# BatchC.net
KiCad netlist of a schematic drawn in EAGLE
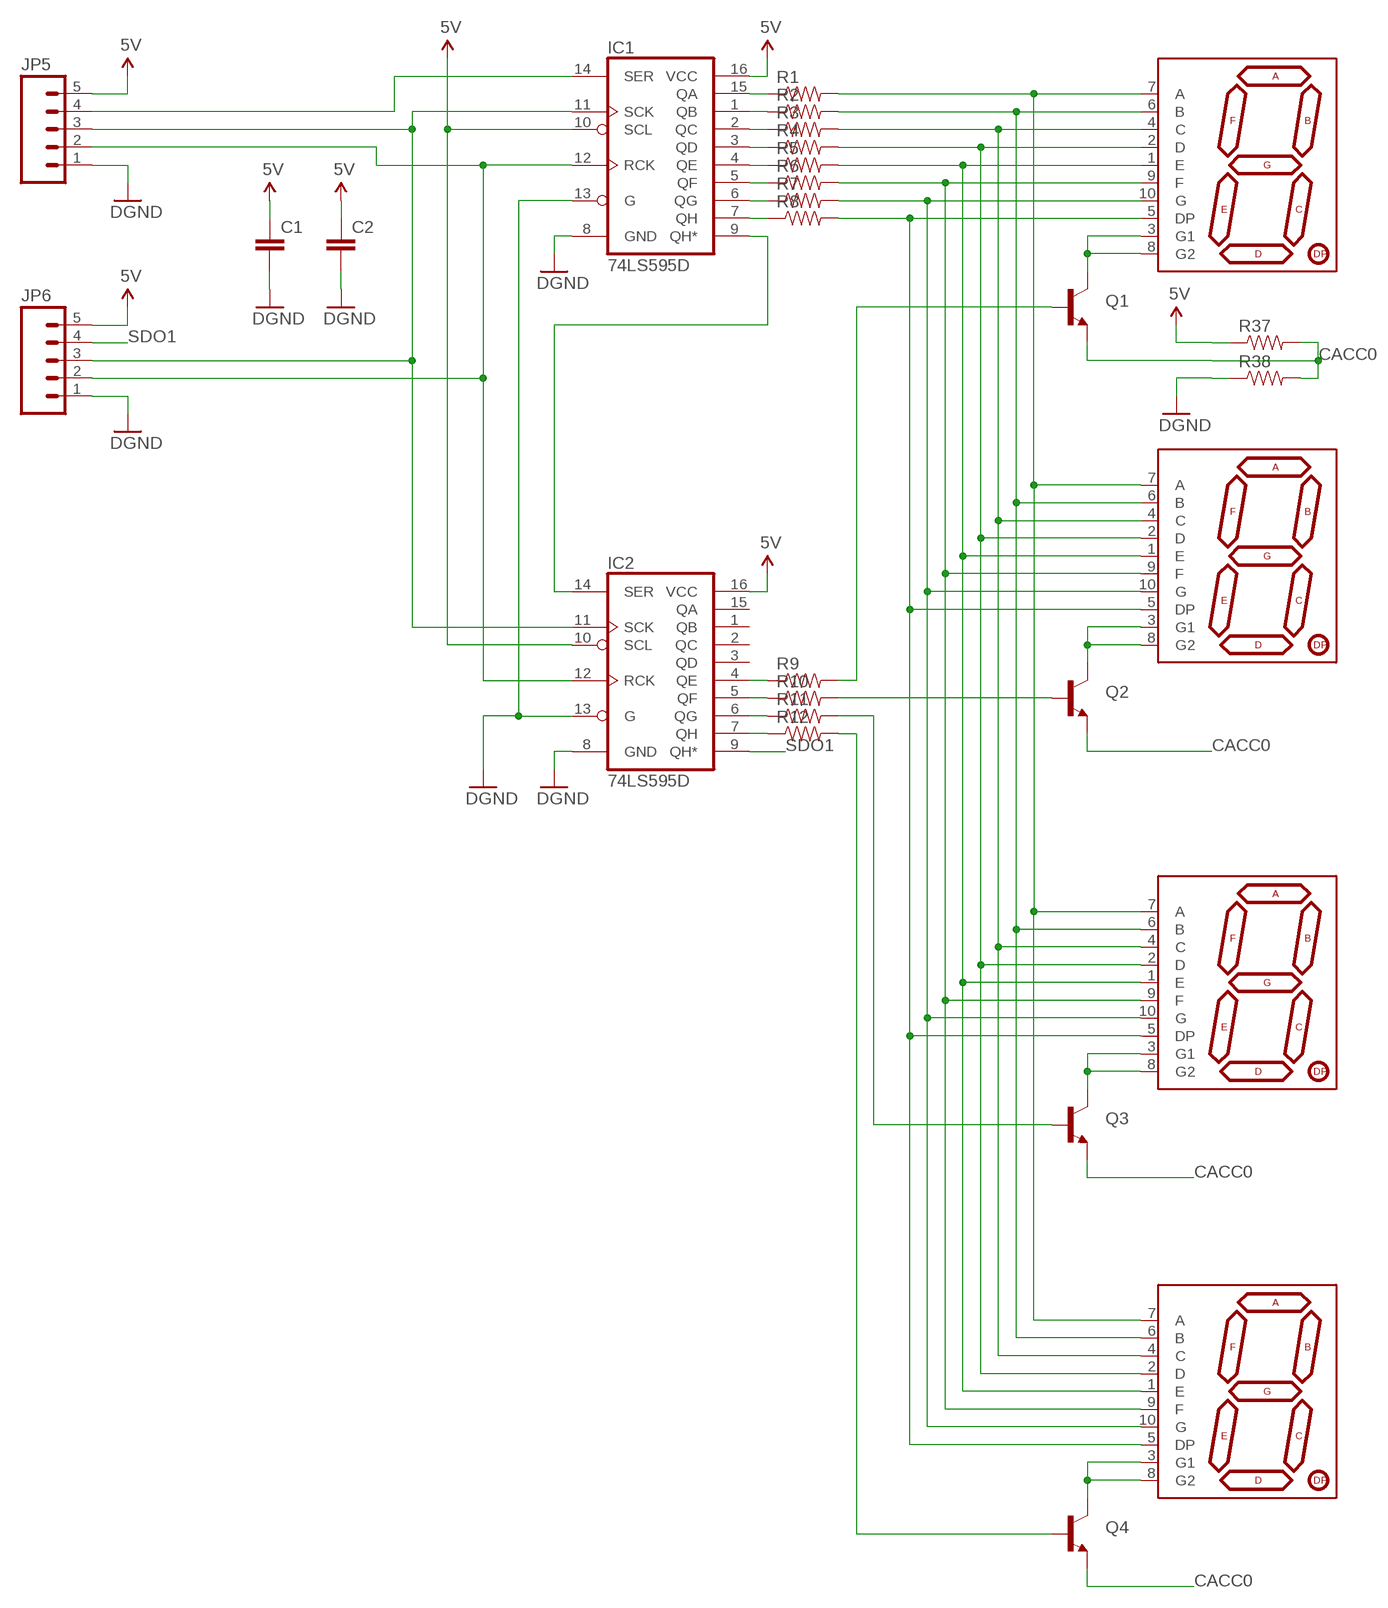
[diagram p0: schematic, sheet 1]
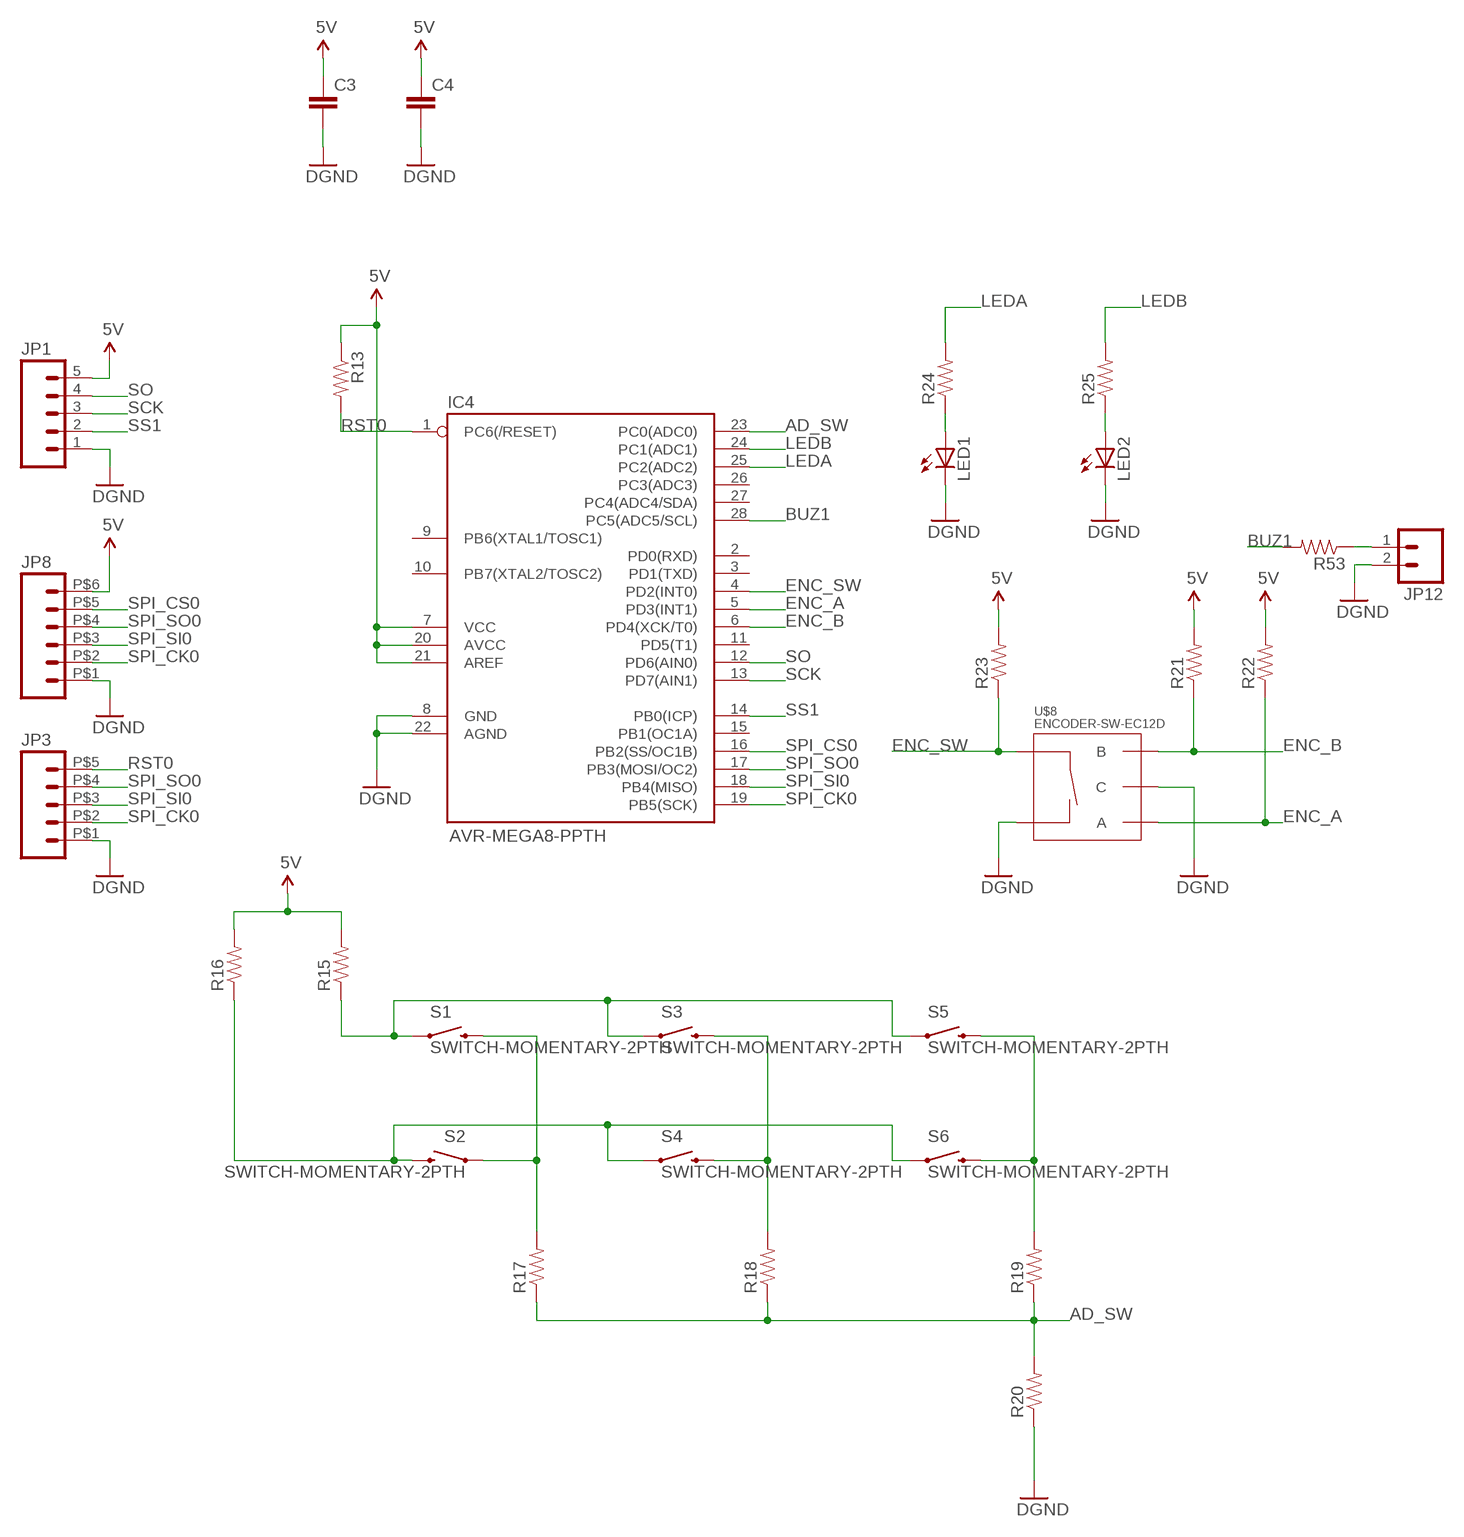
[diagram p1: schematic, sheet 2]
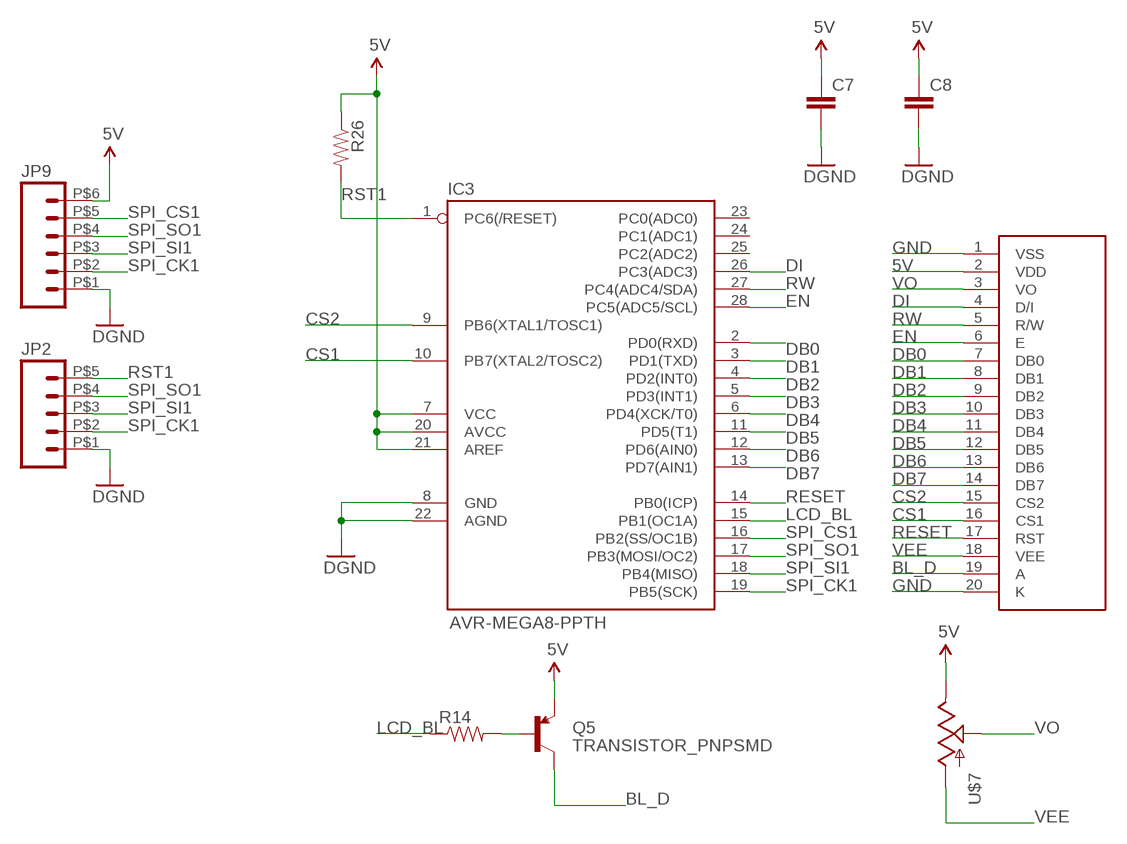
[diagram p2: schematic, sheet 3]
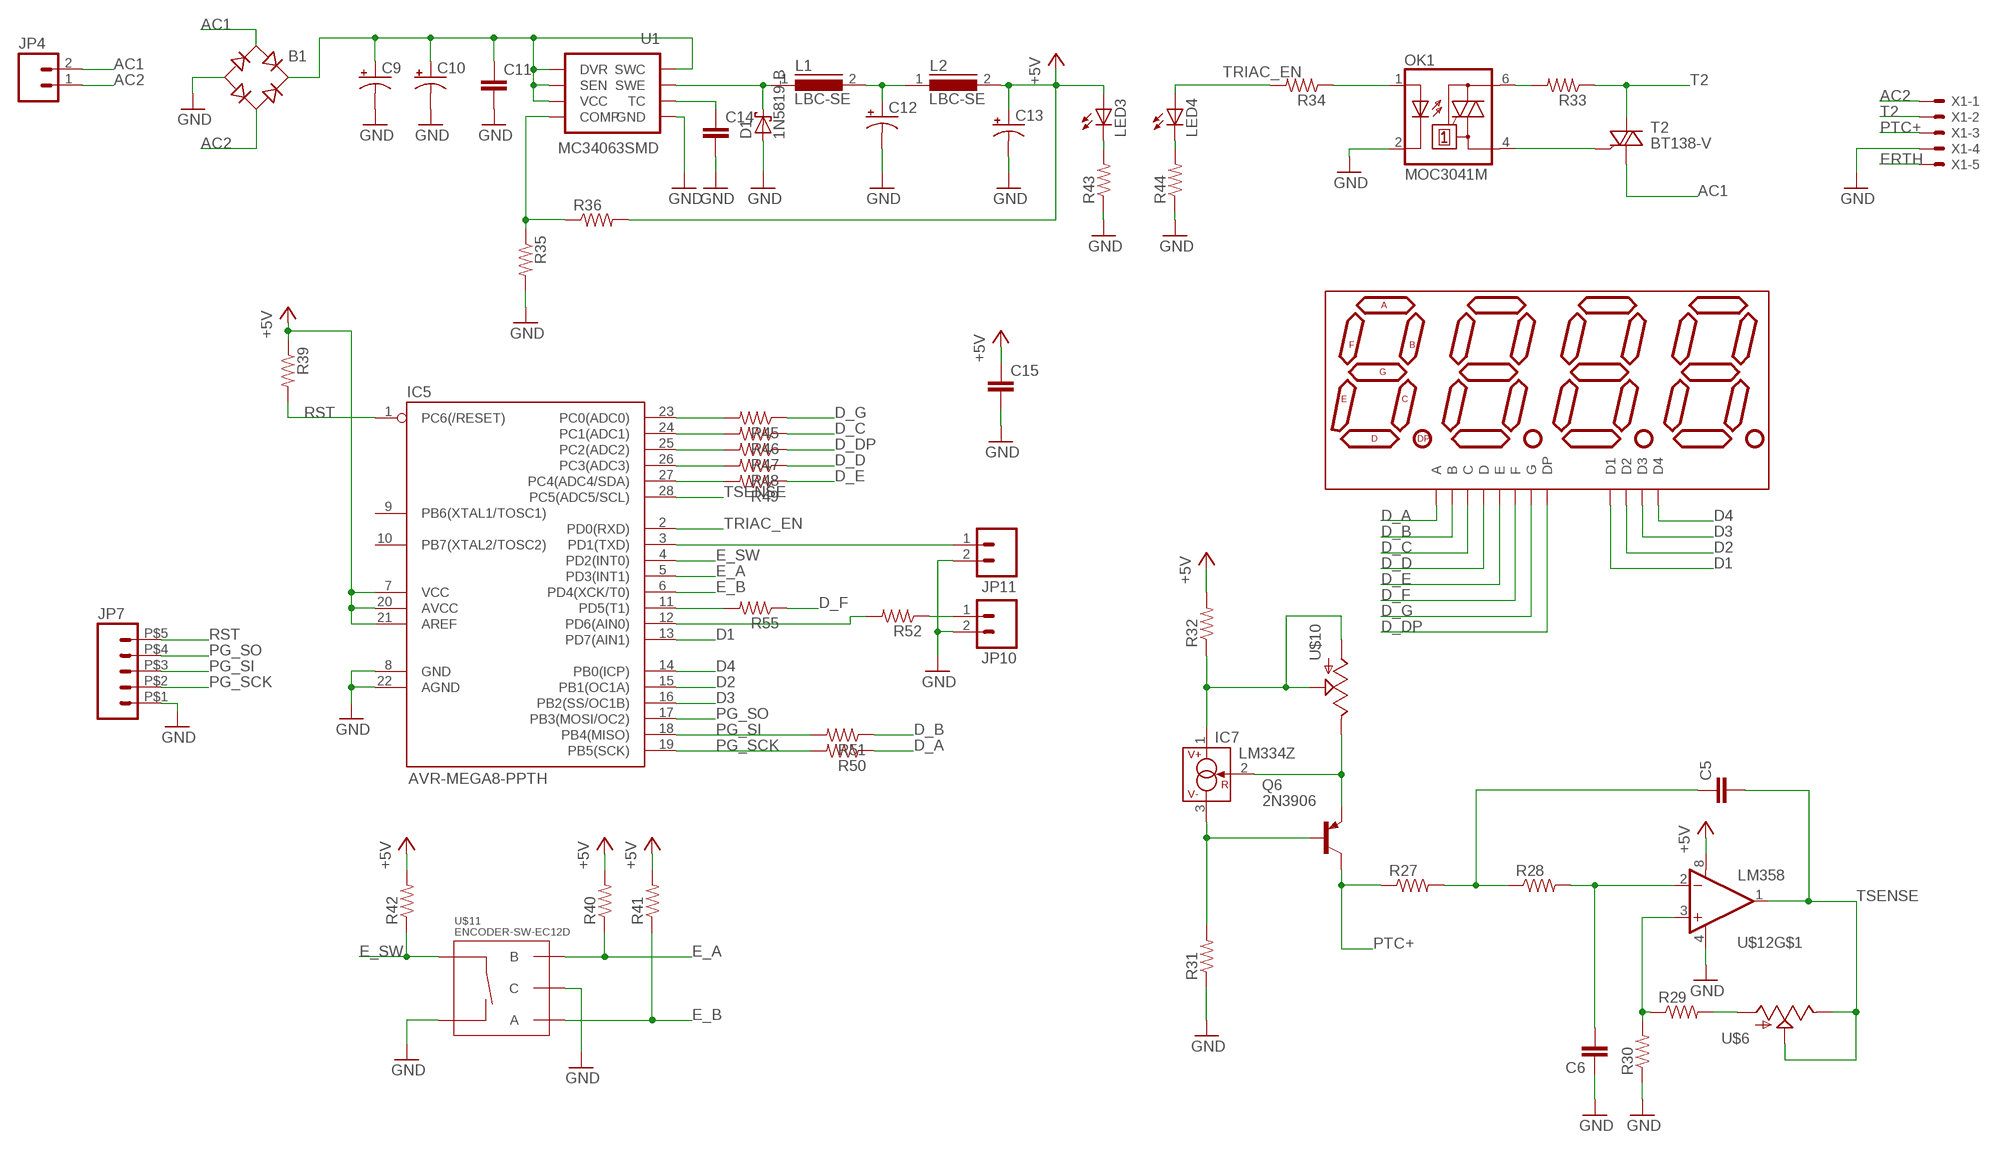
[diagram p3: schematic, sheet 4]
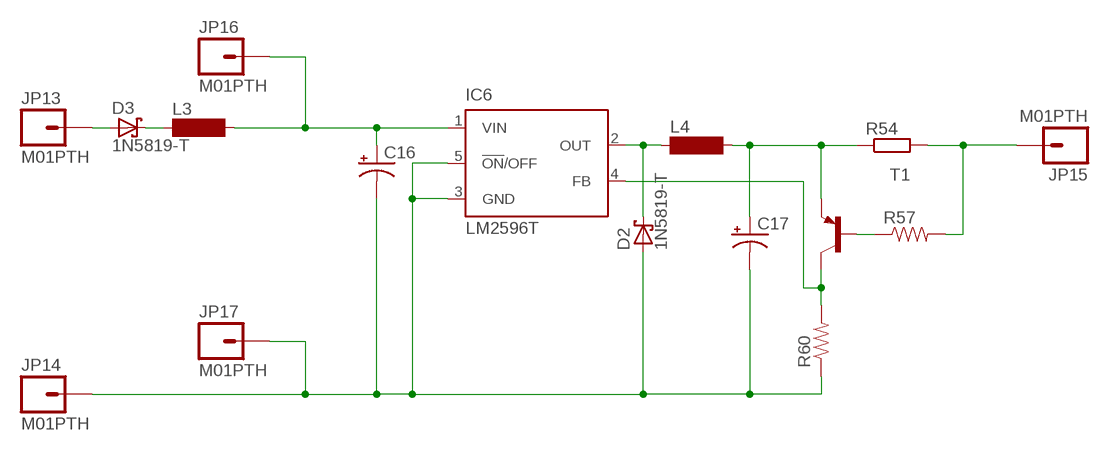
[diagram p4: schematic, sheet 5]

(export (version "E")
  (design (tool "Eeschema 10.0.6"))
  (components
    (comp (ref "C1")
      (value "CAP1206")
      (footprint "eagle-import:1206")
      (libsource (lib "eagle-import") (part "CAP1206"))
    )
    (comp (ref "C2")
      (value "CAP1206")
      (footprint "eagle-import:1206")
      (libsource (lib "eagle-import") (part "CAP1206"))
    )
    (comp (ref "IC1")
      (value "74LS595D")
      (footprint "eagle-import:SO16")
      (libsource (lib "eagle-import") (part "74595DLS"))
    )
    (comp (ref "IC2")
      (value "74LS595D")
      (footprint "eagle-import:SO16")
      (libsource (lib "eagle-import") (part "74595DLS"))
    )
    (comp (ref "JP5")
      (value "M05PTH")
      (footprint "eagle-import:1X05")
      (libsource (lib "eagle-import") (part "M05PTH"))
    )
    (comp (ref "JP6")
      (value "M05PTH")
      (footprint "eagle-import:1X05")
      (libsource (lib "eagle-import") (part "M05PTH"))
    )
    (comp (ref "Q1")
      (value "TRANSISTOR_NPNSOT23")
      (footprint "eagle-import:SOT23")
      (libsource (lib "eagle-import") (part "TRANSISTOR_NPNSOT23"))
    )
    (comp (ref "Q2")
      (value "TRANSISTOR_NPNSOT23")
      (footprint "eagle-import:SOT23")
      (libsource (lib "eagle-import") (part "TRANSISTOR_NPNSOT23"))
    )
    (comp (ref "Q3")
      (value "TRANSISTOR_NPNSOT23")
      (footprint "eagle-import:SOT23")
      (libsource (lib "eagle-import") (part "TRANSISTOR_NPNSOT23"))
    )
    (comp (ref "Q4")
      (value "TRANSISTOR_NPNSOT23")
      (footprint "eagle-import:SOT23")
      (libsource (lib "eagle-import") (part "TRANSISTOR_NPNSOT23"))
    )
    (comp (ref "R1")
      (value "RESISTOR0805-RES")
      (footprint "eagle-import:0805")
      (libsource (lib "eagle-import") (part "RESISTOR0805-RES"))
    )
    (comp (ref "R2")
      (value "RESISTOR0805-RES")
      (footprint "eagle-import:0805")
      (libsource (lib "eagle-import") (part "RESISTOR0805-RES"))
    )
    (comp (ref "R3")
      (value "RESISTOR0805-RES")
      (footprint "eagle-import:0805")
      (libsource (lib "eagle-import") (part "RESISTOR0805-RES"))
    )
    (comp (ref "R4")
      (value "RESISTOR0805-RES")
      (footprint "eagle-import:0805")
      (libsource (lib "eagle-import") (part "RESISTOR0805-RES"))
    )
    (comp (ref "R5")
      (value "RESISTOR0805-RES")
      (footprint "eagle-import:0805")
      (libsource (lib "eagle-import") (part "RESISTOR0805-RES"))
    )
    (comp (ref "R6")
      (value "RESISTOR0805-RES")
      (footprint "eagle-import:0805")
      (libsource (lib "eagle-import") (part "RESISTOR0805-RES"))
    )
    (comp (ref "R7")
      (value "RESISTOR0805-RES")
      (footprint "eagle-import:0805")
      (libsource (lib "eagle-import") (part "RESISTOR0805-RES"))
    )
    (comp (ref "R8")
      (value "RESISTOR0805-RES")
      (footprint "eagle-import:0805")
      (libsource (lib "eagle-import") (part "RESISTOR0805-RES"))
    )
    (comp (ref "R9")
      (value "RESISTOR0805-RES")
      (footprint "eagle-import:0805")
      (libsource (lib "eagle-import") (part "RESISTOR0805-RES"))
    )
    (comp (ref "R10")
      (value "RESISTOR0805-RES")
      (footprint "eagle-import:0805")
      (libsource (lib "eagle-import") (part "RESISTOR0805-RES"))
    )
    (comp (ref "R11")
      (value "RESISTOR0805-RES")
      (footprint "eagle-import:0805")
      (libsource (lib "eagle-import") (part "RESISTOR0805-RES"))
    )
    (comp (ref "R12")
      (value "RESISTOR0805-RES")
      (footprint "eagle-import:0805")
      (libsource (lib "eagle-import") (part "RESISTOR0805-RES"))
    )
    (comp (ref "R37")
      (value "RESISTOR0805-RES")
      (footprint "eagle-import:0805")
      (libsource (lib "eagle-import") (part "RESISTOR0805-RES"))
    )
    (comp (ref "R38")
      (value "RESISTOR0805-RES")
      (footprint "eagle-import:0805")
      (libsource (lib "eagle-import") (part "RESISTOR0805-RES"))
    )
    (comp (ref "U$1")
      (value "7-SEGMENT-DISPLAYPTH")
      (footprint "eagle-import:7-SEGMENT-DISPLAY")
      (libsource (lib "eagle-import") (part "7-SEGMENT-DISPLAYPTH"))
    )
    (comp (ref "U$2")
      (value "7-SEGMENT-DISPLAYPTH")
      (footprint "eagle-import:7-SEGMENT-DISPLAY")
      (libsource (lib "eagle-import") (part "7-SEGMENT-DISPLAYPTH"))
    )
    (comp (ref "U$3")
      (value "7-SEGMENT-DISPLAYPTH")
      (footprint "eagle-import:7-SEGMENT-DISPLAY")
      (libsource (lib "eagle-import") (part "7-SEGMENT-DISPLAYPTH"))
    )
    (comp (ref "U$4")
      (value "7-SEGMENT-DISPLAYPTH")
      (footprint "eagle-import:7-SEGMENT-DISPLAY")
      (libsource (lib "eagle-import") (part "7-SEGMENT-DISPLAYPTH"))
    )
    (comp (ref "B1")
      (value "RB1A")
      (footprint "eagle-import:RB1A")
      (libsource (lib "eagle-import") (part "RB1A"))
    )
    (comp (ref "C5")
      (value "CAPPTH")
      (footprint "eagle-import:CAP-PTH-SMALL")
      (libsource (lib "eagle-import") (part "CAPPTH"))
    )
    (comp (ref "C6")
      (value "CAPPTH")
      (footprint "eagle-import:CAP-PTH-SMALL")
      (libsource (lib "eagle-import") (part "CAPPTH"))
    )
    (comp (ref "C9")
      (value "CAP_POLPTH1")
      (footprint "eagle-import:CPOL-RADIAL-100UF-25V")
      (libsource (lib "eagle-import") (part "CAP_POLPTH1"))
    )
    (comp (ref "C10")
      (value "CAP_POLPTH1")
      (footprint "eagle-import:CPOL-RADIAL-100UF-25V")
      (libsource (lib "eagle-import") (part "CAP_POLPTH1"))
    )
    (comp (ref "C11")
      (value "CAP1206")
      (footprint "eagle-import:1206")
      (libsource (lib "eagle-import") (part "CAP1206"))
    )
    (comp (ref "C12")
      (value "CAP_POLPTH1")
      (footprint "eagle-import:CPOL-RADIAL-100UF-25V")
      (libsource (lib "eagle-import") (part "CAP_POLPTH1"))
    )
    (comp (ref "C13")
      (value "CAP_POLPTH1")
      (footprint "eagle-import:CPOL-RADIAL-100UF-25V")
      (libsource (lib "eagle-import") (part "CAP_POLPTH1"))
    )
    (comp (ref "C14")
      (value "CAP1206")
      (footprint "eagle-import:1206")
      (libsource (lib "eagle-import") (part "CAP1206"))
    )
    (comp (ref "C15")
      (value "CAP1206")
      (footprint "eagle-import:1206")
      (libsource (lib "eagle-import") (part "CAP1206"))
    )
    (comp (ref "D1")
      (value "1N5819-B")
      (footprint "eagle-import:DO41-7.6")
      (libsource (lib "eagle-import") (part "1N5819-B"))
    )
    (comp (ref "IC5")
      (value "AVR-MEGA8-PPTH")
      (footprint "eagle-import:DIL28-3")
      (libsource (lib "eagle-import") (part "AVR-MEGA8-PPTH"))
    )
    (comp (ref "IC7")
      (value "LM334Z")
      (footprint "eagle-import:TO92")
      (libsource (lib "eagle-import") (part "LM34Z3"))
    )
    (comp (ref "JP4")
      (value "M023.5MM")
      (footprint "eagle-import:SCREWTERMINAL-3.5MM-2")
      (libsource (lib "eagle-import") (part "M023.5MM"))
    )
    (comp (ref "JP7")
      (value "M05")
      (footprint "eagle-import:1X05_SMALLPADS")
      (libsource (lib "eagle-import") (part "M05"))
    )
    (comp (ref "JP10")
      (value "M02PTH")
      (footprint "eagle-import:1X02")
      (libsource (lib "eagle-import") (part "M02PTH"))
    )
    (comp (ref "JP11")
      (value "M02PTH")
      (footprint "eagle-import:1X02")
      (libsource (lib "eagle-import") (part "M02PTH"))
    )
    (comp (ref "L1")
      (value "LBC-SE")
      (footprint "eagle-import:LBC-SE")
      (libsource (lib "eagle-import") (part "LBC-SE"))
    )
    (comp (ref "L2")
      (value "LBC-SE")
      (footprint "eagle-import:LBC-SE")
      (libsource (lib "eagle-import") (part "LBC-SE"))
    )
    (comp (ref "LED3")
      (value "LED3MM")
      (footprint "eagle-import:LED3MM")
      (libsource (lib "eagle-import") (part "LED3MM"))
    )
    (comp (ref "LED4")
      (value "LED3MM")
      (footprint "eagle-import:LED3MM")
      (libsource (lib "eagle-import") (part "LED3MM"))
    )
    (comp (ref "OK1")
      (value "MOC3041M")
      (footprint "eagle-import:DIL06")
      (fields (field (name "MF") "FAIRCHILD SEMICONDUCTOR"))
      (libsource (lib "eagle-import") (part "MOC3041M"))
    )
    (comp (ref "Q6")
      (value "2N3906")
      (footprint "eagle-import:TO92")
      (libsource (lib "eagle-import") (part "2N3906"))
    )
    (comp (ref "R27")
      (value "RESISTOR0603-RES")
      (footprint "eagle-import:0603-RES")
      (libsource (lib "eagle-import") (part "SparkFun-Resistors_RESISTOR0603-RES"))
    )
    (comp (ref "R28")
      (value "RESISTOR0603-RES")
      (footprint "eagle-import:0603-RES")
      (libsource (lib "eagle-import") (part "SparkFun-Resistors_RESISTOR0603-RES"))
    )
    (comp (ref "R29")
      (value "RESISTOR0603-RES")
      (footprint "eagle-import:0603-RES")
      (libsource (lib "eagle-import") (part "SparkFun-Resistors_RESISTOR0603-RES"))
    )
    (comp (ref "R30")
      (value "RESISTOR0603-RES")
      (footprint "eagle-import:0603-RES")
      (libsource (lib "eagle-import") (part "SparkFun-Resistors_RESISTOR0603-RES"))
    )
    (comp (ref "R31")
      (value "RESISTOR0603-RES")
      (footprint "eagle-import:0603-RES")
      (libsource (lib "eagle-import") (part "SparkFun-Resistors_RESISTOR0603-RES"))
    )
    (comp (ref "R32")
      (value "RESISTOR0603-RES")
      (footprint "eagle-import:0603-RES")
      (libsource (lib "eagle-import") (part "SparkFun-Resistors_RESISTOR0603-RES"))
    )
    (comp (ref "R33")
      (value "RESISTOR0603-RES")
      (footprint "eagle-import:0603-RES")
      (libsource (lib "eagle-import") (part "SparkFun-Resistors_RESISTOR0603-RES"))
    )
    (comp (ref "R34")
      (value "RESISTOR0603-RES")
      (footprint "eagle-import:0603-RES")
      (libsource (lib "eagle-import") (part "SparkFun-Resistors_RESISTOR0603-RES"))
    )
    (comp (ref "R35")
      (value "RESISTOR0603-RES")
      (footprint "eagle-import:0603-RES")
      (libsource (lib "eagle-import") (part "SparkFun-Resistors_RESISTOR0603-RES"))
    )
    (comp (ref "R36")
      (value "RESISTOR0603-RES")
      (footprint "eagle-import:0603-RES")
      (libsource (lib "eagle-import") (part "SparkFun-Resistors_RESISTOR0603-RES"))
    )
    (comp (ref "R39")
      (value "RESISTOR0603-RES")
      (footprint "eagle-import:0603-RES")
      (libsource (lib "eagle-import") (part "SparkFun-Resistors_RESISTOR0603-RES"))
    )
    (comp (ref "R40")
      (value "RESISTOR0603-RES")
      (footprint "eagle-import:0603-RES")
      (libsource (lib "eagle-import") (part "SparkFun-Resistors_RESISTOR0603-RES"))
    )
    (comp (ref "R41")
      (value "RESISTOR0603-RES")
      (footprint "eagle-import:0603-RES")
      (libsource (lib "eagle-import") (part "SparkFun-Resistors_RESISTOR0603-RES"))
    )
    (comp (ref "R42")
      (value "RESISTOR0603-RES")
      (footprint "eagle-import:0603-RES")
      (libsource (lib "eagle-import") (part "SparkFun-Resistors_RESISTOR0603-RES"))
    )
    (comp (ref "R43")
      (value "RESISTOR0603-RES")
      (footprint "eagle-import:0603-RES")
      (libsource (lib "eagle-import") (part "SparkFun-Resistors_RESISTOR0603-RES"))
    )
    (comp (ref "R44")
      (value "RESISTOR0603-RES")
      (footprint "eagle-import:0603-RES")
      (libsource (lib "eagle-import") (part "SparkFun-Resistors_RESISTOR0603-RES"))
    )
    (comp (ref "R45")
      (value "RESISTOR0603-RES")
      (footprint "eagle-import:0603-RES")
      (libsource (lib "eagle-import") (part "SparkFun-Resistors_RESISTOR0603-RES"))
    )
    (comp (ref "R46")
      (value "RESISTOR0603-RES")
      (footprint "eagle-import:0603-RES")
      (libsource (lib "eagle-import") (part "SparkFun-Resistors_RESISTOR0603-RES"))
    )
    (comp (ref "R47")
      (value "RESISTOR0603-RES")
      (footprint "eagle-import:0603-RES")
      (libsource (lib "eagle-import") (part "SparkFun-Resistors_RESISTOR0603-RES"))
    )
    (comp (ref "R48")
      (value "RESISTOR0603-RES")
      (footprint "eagle-import:0603-RES")
      (libsource (lib "eagle-import") (part "SparkFun-Resistors_RESISTOR0603-RES"))
    )
    (comp (ref "R49")
      (value "RESISTOR0603-RES")
      (footprint "eagle-import:0603-RES")
      (libsource (lib "eagle-import") (part "SparkFun-Resistors_RESISTOR0603-RES"))
    )
    (comp (ref "R50")
      (value "RESISTOR0603-RES")
      (footprint "eagle-import:0603-RES")
      (libsource (lib "eagle-import") (part "SparkFun-Resistors_RESISTOR0603-RES"))
    )
    (comp (ref "R51")
      (value "RESISTOR0603-RES")
      (footprint "eagle-import:0603-RES")
      (libsource (lib "eagle-import") (part "SparkFun-Resistors_RESISTOR0603-RES"))
    )
    (comp (ref "R52")
      (value "RESISTOR0603-RES")
      (footprint "eagle-import:0603-RES")
      (libsource (lib "eagle-import") (part "SparkFun-Resistors_RESISTOR0603-RES"))
    )
    (comp (ref "R55")
      (value "RESISTOR0603-RES")
      (footprint "eagle-import:0603-RES")
      (libsource (lib "eagle-import") (part "SparkFun-Resistors_RESISTOR0603-RES"))
    )
    (comp (ref "T2")
      (value "BT138-V")
      (footprint "eagle-import:TO220BV")
      (libsource (lib "eagle-import") (part "BT138-V"))
    )
    (comp (ref "U$5")
      (value "7-SEGMENT-4DIGIT-COUNTER")
      (footprint "eagle-import:7-SEGMENT-4DIGIT-TPS")
      (libsource (lib "eagle-import") (part "7-SEGMENT-4DIGIT-COUNTER"))
    )
    (comp (ref "U$6")
      (value "POTTRIM")
      (footprint "eagle-import:TRIM_POT")
      (libsource (lib "eagle-import") (part "POTTRIM"))
    )
    (comp (ref "U$10")
      (value "POTTRIM")
      (footprint "eagle-import:TRIM_POT")
      (libsource (lib "eagle-import") (part "POTTRIM"))
    )
    (comp (ref "U$11")
      (value "ENCODER-SW-EC12D")
      (footprint "eagle-import:ENCODER-SW-EC12D")
      (libsource (lib "eagle-import") (part "ENCODER-SW-EC12D"))
    )
    (comp (ref "U$12")
      (value "LM358")
      (footprint "eagle-import:DIP08")
      (libsource (lib "eagle-import") (part "LM358"))
    )
    (comp (ref "U1")
      (value "MC34063SMD")
      (footprint "eagle-import:SO08")
      (libsource (lib "eagle-import") (part "MC34063SMD"))
    )
    (comp (ref "X1")
      (value "KK-156-5")
      (footprint "eagle-import:KK-156-5")
      (libsource (lib "eagle-import") (part "KK-156-5"))
    )
    (comp (ref "C3")
      (value "CAP1206")
      (footprint "eagle-import:1206")
      (libsource (lib "eagle-import") (part "CAP1206"))
    )
    (comp (ref "C4")
      (value "CAP1206")
      (footprint "eagle-import:1206")
      (libsource (lib "eagle-import") (part "CAP1206"))
    )
    (comp (ref "IC4")
      (value "AVR-MEGA8-PPTH")
      (footprint "eagle-import:DIL28-3")
      (libsource (lib "eagle-import") (part "AVR-MEGA8-PPTH"))
    )
    (comp (ref "JP1")
      (value "M05PTH")
      (footprint "eagle-import:1X05")
      (libsource (lib "eagle-import") (part "M05PTH"))
    )
    (comp (ref "JP3")
      (value "M05")
      (footprint "eagle-import:1X05_SMALLPADS")
      (libsource (lib "eagle-import") (part "M05"))
    )
    (comp (ref "JP8")
      (value "M06")
      (footprint "eagle-import:1X06_SMALLPADS")
      (libsource (lib "eagle-import") (part "M06"))
    )
    (comp (ref "JP12")
      (value "M02PTH")
      (footprint "eagle-import:1X02")
      (libsource (lib "eagle-import") (part "M02PTH"))
    )
    (comp (ref "LED1")
      (value "LED3MM")
      (footprint "eagle-import:LED3MM")
      (libsource (lib "eagle-import") (part "LED3MM"))
    )
    (comp (ref "LED2")
      (value "LED3MM")
      (footprint "eagle-import:LED3MM")
      (libsource (lib "eagle-import") (part "LED3MM"))
    )
    (comp (ref "R13")
      (value "RESISTOR0805-RES")
      (footprint "eagle-import:0805")
      (libsource (lib "eagle-import") (part "RESISTOR0805-RES"))
    )
    (comp (ref "R15")
      (value "RESISTOR0805-RES")
      (footprint "eagle-import:0805")
      (libsource (lib "eagle-import") (part "RESISTOR0805-RES"))
    )
    (comp (ref "R16")
      (value "RESISTOR0805-RES")
      (footprint "eagle-import:0805")
      (libsource (lib "eagle-import") (part "RESISTOR0805-RES"))
    )
    (comp (ref "R17")
      (value "RESISTOR0805-RES")
      (footprint "eagle-import:0805")
      (libsource (lib "eagle-import") (part "RESISTOR0805-RES"))
    )
    (comp (ref "R18")
      (value "RESISTOR0805-RES")
      (footprint "eagle-import:0805")
      (libsource (lib "eagle-import") (part "RESISTOR0805-RES"))
    )
    (comp (ref "R19")
      (value "RESISTOR0805-RES")
      (footprint "eagle-import:0805")
      (libsource (lib "eagle-import") (part "RESISTOR0805-RES"))
    )
    (comp (ref "R20")
      (value "RESISTOR0805-RES")
      (footprint "eagle-import:0805")
      (libsource (lib "eagle-import") (part "RESISTOR0805-RES"))
    )
    (comp (ref "R21")
      (value "RESISTOR0805-RES")
      (footprint "eagle-import:0805")
      (libsource (lib "eagle-import") (part "RESISTOR0805-RES"))
    )
    (comp (ref "R22")
      (value "RESISTOR0805-RES")
      (footprint "eagle-import:0805")
      (libsource (lib "eagle-import") (part "RESISTOR0805-RES"))
    )
    (comp (ref "R23")
      (value "RESISTOR0805-RES")
      (footprint "eagle-import:0805")
      (libsource (lib "eagle-import") (part "RESISTOR0805-RES"))
    )
    (comp (ref "R24")
      (value "RESISTOR0805-RES")
      (footprint "eagle-import:0805")
      (libsource (lib "eagle-import") (part "RESISTOR0805-RES"))
    )
    (comp (ref "R25")
      (value "RESISTOR0805-RES")
      (footprint "eagle-import:0805")
      (libsource (lib "eagle-import") (part "RESISTOR0805-RES"))
    )
    (comp (ref "R53")
      (value "RESISTOR0805-RES")
      (footprint "eagle-import:0805")
      (libsource (lib "eagle-import") (part "RESISTOR0805-RES"))
    )
    (comp (ref "S1")
      (value "SWITCH-MOMENTARY-2PTH")
      (footprint "eagle-import:TACTILE-PTH")
      (libsource (lib "eagle-import") (part "SWITCH-MOMENTARY-2PTH"))
    )
    (comp (ref "S2")
      (value "SWITCH-MOMENTARY-2PTH")
      (footprint "eagle-import:TACTILE-PTH")
      (libsource (lib "eagle-import") (part "SWITCH-MOMENTARY-2PTH"))
    )
    (comp (ref "S3")
      (value "SWITCH-MOMENTARY-2PTH")
      (footprint "eagle-import:TACTILE-PTH")
      (libsource (lib "eagle-import") (part "SWITCH-MOMENTARY-2PTH"))
    )
    (comp (ref "S4")
      (value "SWITCH-MOMENTARY-2PTH")
      (footprint "eagle-import:TACTILE-PTH")
      (libsource (lib "eagle-import") (part "SWITCH-MOMENTARY-2PTH"))
    )
    (comp (ref "S5")
      (value "SWITCH-MOMENTARY-2PTH")
      (footprint "eagle-import:TACTILE-PTH")
      (libsource (lib "eagle-import") (part "SWITCH-MOMENTARY-2PTH"))
    )
    (comp (ref "S6")
      (value "SWITCH-MOMENTARY-2PTH")
      (footprint "eagle-import:TACTILE-PTH")
      (libsource (lib "eagle-import") (part "SWITCH-MOMENTARY-2PTH"))
    )
    (comp (ref "U$8")
      (value "ENCODER-SW-EC12D")
      (footprint "eagle-import:ENCODER-SW-EC12D")
      (libsource (lib "eagle-import") (part "ENCODER-SW-EC12D"))
    )
    (comp (ref "C7")
      (value "CAP1206")
      (footprint "eagle-import:1206")
      (libsource (lib "eagle-import") (part "CAP1206"))
    )
    (comp (ref "C8")
      (value "CAP1206")
      (footprint "eagle-import:1206")
      (libsource (lib "eagle-import") (part "CAP1206"))
    )
    (comp (ref "IC3")
      (value "AVR-MEGA8-PPTH")
      (footprint "eagle-import:DIL28-3")
      (libsource (lib "eagle-import") (part "AVR-MEGA8-PPTH"))
    )
    (comp (ref "JP2")
      (value "M05")
      (footprint "eagle-import:1X05_SMALLPADS")
      (libsource (lib "eagle-import") (part "M05"))
    )
    (comp (ref "JP9")
      (value "M06")
      (footprint "eagle-import:1X06_SMALLPADS")
      (libsource (lib "eagle-import") (part "M06"))
    )
    (comp (ref "Q5")
      (value "TRANSISTOR_PNPSMD")
      (footprint "eagle-import:SOT23-3")
      (libsource (lib "eagle-import") (part "TRANSISTOR_PNPSMD"))
    )
    (comp (ref "R14")
      (value "RESISTOR0805-RES")
      (footprint "eagle-import:0805")
      (libsource (lib "eagle-import") (part "RESISTOR0805-RES"))
    )
    (comp (ref "R26")
      (value "RESISTOR0805-RES")
      (footprint "eagle-import:0805")
      (libsource (lib "eagle-import") (part "RESISTOR0805-RES"))
    )
    (comp (ref "U$7")
      (value "POTTRIM")
      (footprint "eagle-import:TRIM_POT")
      (libsource (lib "eagle-import") (part "POTTRIM"))
    )
    (comp (ref "U$9")
      (value "LCD-G12864BARE")
      (footprint "eagle-import:1X20")
      (libsource (lib "eagle-import") (part "LCD-G12864BARE"))
    )
    (comp (ref "C16")
      (value "CAP_POLPTH1")
      (footprint "eagle-import:CPOL-RADIAL-100UF-25V")
      (libsource (lib "eagle-import") (part "SparkFun-Passives_CAP_POLPTH1"))
    )
    (comp (ref "C17")
      (value "CAP_POLPTH1")
      (footprint "eagle-import:CPOL-RADIAL-100UF-25V")
      (libsource (lib "eagle-import") (part "SparkFun-Passives_CAP_POLPTH1"))
    )
    (comp (ref "D2")
      (value "1N5819-T")
      (footprint "eagle-import:DO41-7.6")
      (libsource (lib "eagle-import") (part "1N5819-T"))
    )
    (comp (ref "D3")
      (value "1N5819-T")
      (footprint "eagle-import:DO41-7.6")
      (libsource (lib "eagle-import") (part "1N5819-T"))
    )
    (comp (ref "IC6")
      (value "LM2596T")
      (footprint "eagle-import:T05D")
      (fields (field (name "MPN") "LM2596T-ADJ/LF02"))
      (libsource (lib "eagle-import") (part "LM2596T"))
    )
    (comp (ref "JP13")
      (value "M01PTH")
      (footprint "eagle-import:1X01")
      (libsource (lib "eagle-import") (part "M01PTH"))
    )
    (comp (ref "JP14")
      (value "M01PTH")
      (footprint "eagle-import:1X01")
      (libsource (lib "eagle-import") (part "M01PTH"))
    )
    (comp (ref "JP15")
      (value "M01PTH")
      (footprint "eagle-import:1X01")
      (libsource (lib "eagle-import") (part "M01PTH"))
    )
    (comp (ref "JP16")
      (value "M01PTH")
      (footprint "eagle-import:1X01")
      (libsource (lib "eagle-import") (part "M01PTH"))
    )
    (comp (ref "JP17")
      (value "M01PTH")
      (footprint "eagle-import:1X01")
      (libsource (lib "eagle-import") (part "M01PTH"))
    )
    (comp (ref "L3")
      (value "BS11")
      (footprint "eagle-import:BS11")
      (libsource (lib "eagle-import") (part "BS11"))
    )
    (comp (ref "L4")
      (value "BS11")
      (footprint "eagle-import:BS11")
      (libsource (lib "eagle-import") (part "BS11"))
    )
    (comp (ref "R54")
      (value "R-EU_0204/2V")
      (footprint "eagle-import:0204V")
      (libsource (lib "eagle-import") (part "R-EU_0204/2V"))
    )
    (comp (ref "R57")
      (value "RESISTOR1206")
      (footprint "eagle-import:1206")
      (libsource (lib "eagle-import") (part "SparkFun-Resistors_RESISTOR1206"))
    )
    (comp (ref "R60")
      (value "RESISTOR1206")
      (footprint "eagle-import:1206")
      (libsource (lib "eagle-import") (part "SparkFun-Resistors_RESISTOR1206"))
    )
    (comp (ref "T1")
      (value "BC857C-PNP-SOT23-BEC")
      (footprint "eagle-import:SOT23-BEC")
      (libsource (lib "eagle-import") (part "-PNP-SOT23-BECBC857C"))
    )
  )
  (nets
    (net (code "1") (name "+5V") (class "Default")
      (node (ref "C13") (pin "1") (pinfunction "+_1") (pintype "passive"))
      (node (ref "C15") (pin "1") (pinfunction "1_1") (pintype "passive"))
      (node (ref "IC5") (pin "20") (pinfunction "AVCC_20") (pintype "bidirectional"))
      (node (ref "IC5") (pin "21") (pinfunction "AREF_21") (pintype "bidirectional"))
      (node (ref "IC5") (pin "7") (pinfunction "VCC_7") (pintype "bidirectional"))
      (node (ref "L2") (pin "2") (pinfunction "2_2") (pintype "passive"))
      (node (ref "LED3") (pin "A") (pinfunction "A_A") (pintype "passive"))
      (node (ref "R32") (pin "2") (pinfunction "2_2") (pintype "passive"))
      (node (ref "R36") (pin "2") (pinfunction "2_2") (pintype "passive"))
      (node (ref "R39") (pin "1") (pinfunction "1_1") (pintype "passive"))
      (node (ref "R40") (pin "2") (pinfunction "2_2") (pintype "passive"))
      (node (ref "R41") (pin "2") (pinfunction "2_2") (pintype "passive"))
      (node (ref "R42") (pin "2") (pinfunction "2_2") (pintype "passive"))
      (node (ref "U$12") (pin "8") (pinfunction "V+_8") (pintype "power_in"))
    )
    (net (code "2") (name "5V") (class "Default")
      (node (ref "C1") (pin "1") (pinfunction "1_1") (pintype "passive"))
      (node (ref "C2") (pin "1") (pinfunction "1_1") (pintype "passive"))
      (node (ref "C3") (pin "1") (pinfunction "1_1") (pintype "passive"))
      (node (ref "C4") (pin "1") (pinfunction "1_1") (pintype "passive"))
      (node (ref "C7") (pin "1") (pinfunction "1_1") (pintype "passive"))
      (node (ref "C8") (pin "1") (pinfunction "1_1") (pintype "passive"))
      (node (ref "IC1") (pin "10") (pinfunction "SCL_10") (pintype "input"))
      (node (ref "IC1") (pin "16") (pinfunction "VCC_16") (pintype "power_in"))
      (node (ref "IC2") (pin "10") (pinfunction "SCL_10") (pintype "input"))
      (node (ref "IC2") (pin "16") (pinfunction "VCC_16") (pintype "power_in"))
      (node (ref "IC3") (pin "20") (pinfunction "AVCC_20") (pintype "bidirectional"))
      (node (ref "IC3") (pin "21") (pinfunction "AREF_21") (pintype "bidirectional"))
      (node (ref "IC3") (pin "7") (pinfunction "VCC_7") (pintype "bidirectional"))
      (node (ref "IC4") (pin "20") (pinfunction "AVCC_20") (pintype "bidirectional"))
      (node (ref "IC4") (pin "21") (pinfunction "AREF_21") (pintype "bidirectional"))
      (node (ref "IC4") (pin "7") (pinfunction "VCC_7") (pintype "bidirectional"))
      (node (ref "JP1") (pin "5") (pinfunction "5_5") (pintype "passive"))
      (node (ref "JP5") (pin "5") (pinfunction "5_5") (pintype "passive"))
      (node (ref "JP6") (pin "5") (pinfunction "5_5") (pintype "passive"))
      (node (ref "JP8") (pin "P$6") (pinfunction "6_P$6") (pintype "passive"))
      (node (ref "JP9") (pin "P$6") (pinfunction "6_P$6") (pintype "passive"))
      (node (ref "Q5") (pin "2") (pinfunction "E_2") (pintype "passive"))
      (node (ref "R13") (pin "1") (pinfunction "1_1") (pintype "passive"))
      (node (ref "R15") (pin "2") (pinfunction "2_2") (pintype "passive"))
      (node (ref "R16") (pin "2") (pinfunction "2_2") (pintype "passive"))
      (node (ref "R21") (pin "2") (pinfunction "2_2") (pintype "passive"))
      (node (ref "R22") (pin "2") (pinfunction "2_2") (pintype "passive"))
      (node (ref "R23") (pin "2") (pinfunction "2_2") (pintype "passive"))
      (node (ref "R26") (pin "1") (pinfunction "1_1") (pintype "passive"))
      (node (ref "R37") (pin "1") (pinfunction "1_1") (pintype "passive"))
      (node (ref "U$7") (pin "2") (pinfunction "E_2") (pintype "passive"))
      (node (ref "U$9") (pin "2") (pinfunction "VDD_2") (pintype "power_in"))
    )
    (net (code "3") (name "AC1") (class "Default")
      (node (ref "B1") (pin "AC1") (pinfunction "AC1_AC1") (pintype "passive"))
      (node (ref "JP4") (pin "2") (pinfunction "2_2") (pintype "passive"))
      (node (ref "T2") (pin "T1") (pinfunction "A1_T1") (pintype "passive"))
    )
    (net (code "4") (name "AC2") (class "Default")
      (node (ref "B1") (pin "AC2") (pinfunction "AC2_AC2") (pintype "passive"))
      (node (ref "JP4") (pin "1") (pinfunction "1_1") (pintype "passive"))
      (node (ref "X1") (pin "1") (pinfunction "S_1") (pintype "passive"))
    )
    (net (code "5") (name "AD_SW") (class "Default")
      (node (ref "IC4") (pin "23") (pinfunction "PC0(ADC0)_23") (pintype "bidirectional"))
      (node (ref "R17") (pin "1") (pinfunction "1_1") (pintype "passive"))
      (node (ref "R18") (pin "1") (pinfunction "1_1") (pintype "passive"))
      (node (ref "R19") (pin "1") (pinfunction "1_1") (pintype "passive"))
      (node (ref "R20") (pin "2") (pinfunction "2_2") (pintype "passive"))
    )
    (net (code "6") (name "BL_D") (class "Default")
      (node (ref "Q5") (pin "3") (pinfunction "C_3") (pintype "passive"))
      (node (ref "U$9") (pin "19") (pinfunction "A_19") (pintype "power_in"))
    )
    (net (code "7") (name "BUZ1") (class "Default")
      (node (ref "IC4") (pin "28") (pinfunction "PC5(ADC5/SCL)_28") (pintype "bidirectional"))
      (node (ref "R53") (pin "2") (pinfunction "2_2") (pintype "passive"))
    )
    (net (code "8") (name "CACC0") (class "Default")
      (node (ref "Q1") (pin "2") (pinfunction "E_2") (pintype "passive"))
      (node (ref "Q2") (pin "2") (pinfunction "E_2") (pintype "passive"))
      (node (ref "Q3") (pin "2") (pinfunction "E_2") (pintype "passive"))
      (node (ref "Q4") (pin "2") (pinfunction "E_2") (pintype "passive"))
      (node (ref "R37") (pin "2") (pinfunction "2_2") (pintype "passive"))
      (node (ref "R38") (pin "2") (pinfunction "2_2") (pintype "passive"))
    )
    (net (code "9") (name "CS1") (class "Default")
      (node (ref "IC3") (pin "10") (pinfunction "PB7(XTAL2/TOSC2)_10") (pintype "bidirectional"))
      (node (ref "U$9") (pin "16") (pinfunction "CS1_16") (pintype "input"))
    )
    (net (code "10") (name "CS2") (class "Default")
      (node (ref "IC3") (pin "9") (pinfunction "PB6(XTAL1/TOSC1)_9") (pintype "bidirectional"))
      (node (ref "U$9") (pin "15") (pinfunction "CS2_15") (pintype "input"))
    )
    (net (code "11") (name "D1") (class "Default")
      (node (ref "IC5") (pin "13") (pinfunction "PD7(AIN1)_13") (pintype "bidirectional"))
      (node (ref "U$5") (pin "P$12") (pinfunction "D1_P$12") (pintype "bidirectional"))
    )
    (net (code "12") (name "D2") (class "Default")
      (node (ref "IC5") (pin "15") (pinfunction "PB1(OC1A)_15") (pintype "bidirectional"))
      (node (ref "U$5") (pin "P$9") (pinfunction "D2_P$9") (pintype "bidirectional"))
    )
    (net (code "13") (name "D3") (class "Default")
      (node (ref "IC5") (pin "16") (pinfunction "PB2(SS/OC1B)_16") (pintype "bidirectional"))
      (node (ref "U$5") (pin "P$8") (pinfunction "D3_P$8") (pintype "bidirectional"))
    )
    (net (code "14") (name "D4") (class "Default")
      (node (ref "IC5") (pin "14") (pinfunction "PB0(ICP)_14") (pintype "bidirectional"))
      (node (ref "U$5") (pin "P$6") (pinfunction "D4_P$6") (pintype "bidirectional"))
    )
    (net (code "15") (name "DB0") (class "Default")
      (node (ref "IC3") (pin "2") (pinfunction "PD0(RXD)_2") (pintype "bidirectional"))
      (node (ref "U$9") (pin "7") (pinfunction "DB0_7") (pintype "bidirectional"))
    )
    (net (code "16") (name "DB1") (class "Default")
      (node (ref "IC3") (pin "3") (pinfunction "PD1(TXD)_3") (pintype "bidirectional"))
      (node (ref "U$9") (pin "8") (pinfunction "DB1_8") (pintype "bidirectional"))
    )
    (net (code "17") (name "DB2") (class "Default")
      (node (ref "IC3") (pin "4") (pinfunction "PD2(INT0)_4") (pintype "bidirectional"))
      (node (ref "U$9") (pin "9") (pinfunction "DB2_9") (pintype "bidirectional"))
    )
    (net (code "18") (name "DB3") (class "Default")
      (node (ref "IC3") (pin "5") (pinfunction "PD3(INT1)_5") (pintype "bidirectional"))
      (node (ref "U$9") (pin "10") (pinfunction "DB3_10") (pintype "bidirectional"))
    )
    (net (code "19") (name "DB4") (class "Default")
      (node (ref "IC3") (pin "6") (pinfunction "PD4(XCK/T0)_6") (pintype "bidirectional"))
      (node (ref "U$9") (pin "11") (pinfunction "DB4_11") (pintype "bidirectional"))
    )
    (net (code "20") (name "DB5") (class "Default")
      (node (ref "IC3") (pin "11") (pinfunction "PD5(T1)_11") (pintype "bidirectional"))
      (node (ref "U$9") (pin "12") (pinfunction "DB5_12") (pintype "bidirectional"))
    )
    (net (code "21") (name "DB6") (class "Default")
      (node (ref "IC3") (pin "12") (pinfunction "PD6(AIN0)_12") (pintype "bidirectional"))
      (node (ref "U$9") (pin "13") (pinfunction "DB6_13") (pintype "bidirectional"))
    )
    (net (code "22") (name "DB7") (class "Default")
      (node (ref "IC3") (pin "13") (pinfunction "PD7(AIN1)_13") (pintype "bidirectional"))
      (node (ref "U$9") (pin "14") (pinfunction "DB7_14") (pintype "bidirectional"))
    )
    (net (code "23") (name "DI") (class "Default")
      (node (ref "IC3") (pin "26") (pinfunction "PC3(ADC3)_26") (pintype "bidirectional"))
      (node (ref "U$9") (pin "4") (pinfunction "D/I_4") (pintype "input"))
    )
    (net (code "24") (name "D_A") (class "Default")
      (node (ref "R50") (pin "1") (pinfunction "1_1") (pintype "passive"))
      (node (ref "U$5") (pin "P$11") (pinfunction "A_P$11") (pintype "bidirectional"))
    )
    (net (code "25") (name "D_B") (class "Default")
      (node (ref "R51") (pin "1") (pinfunction "1_1") (pintype "passive"))
      (node (ref "U$5") (pin "P$7") (pinfunction "B_P$7") (pintype "bidirectional"))
    )
    (net (code "26") (name "D_C") (class "Default")
      (node (ref "R46") (pin "1") (pinfunction "1_1") (pintype "passive"))
      (node (ref "U$5") (pin "P$4") (pinfunction "C_P$4") (pintype "bidirectional"))
    )
    (net (code "27") (name "D_D") (class "Default")
      (node (ref "R48") (pin "1") (pinfunction "1_1") (pintype "passive"))
      (node (ref "U$5") (pin "P$2") (pinfunction "D_P$2") (pintype "bidirectional"))
    )
    (net (code "28") (name "D_DP") (class "Default")
      (node (ref "R47") (pin "1") (pinfunction "1_1") (pintype "passive"))
      (node (ref "U$5") (pin "P$3") (pinfunction "DP_P$3") (pintype "bidirectional"))
    )
    (net (code "29") (name "D_E") (class "Default")
      (node (ref "R49") (pin "1") (pinfunction "1_1") (pintype "passive"))
      (node (ref "U$5") (pin "P$1") (pinfunction "E_P$1") (pintype "bidirectional"))
    )
    (net (code "30") (name "D_F") (class "Default")
      (node (ref "R55") (pin "1") (pinfunction "1_1") (pintype "passive"))
      (node (ref "U$5") (pin "P$10") (pinfunction "F_P$10") (pintype "bidirectional"))
    )
    (net (code "31") (name "D_G") (class "Default")
      (node (ref "R45") (pin "1") (pinfunction "1_1") (pintype "passive"))
      (node (ref "U$5") (pin "P$5") (pinfunction "G_P$5") (pintype "bidirectional"))
    )
    (net (code "32") (name "EN") (class "Default")
      (node (ref "IC3") (pin "28") (pinfunction "PC5(ADC5/SCL)_28") (pintype "bidirectional"))
      (node (ref "U$9") (pin "6") (pinfunction "E_6") (pintype "input"))
    )
    (net (code "33") (name "ENC_A") (class "Default")
      (node (ref "IC4") (pin "5") (pinfunction "PD3(INT1)_5") (pintype "bidirectional"))
      (node (ref "R22") (pin "1") (pinfunction "1_1") (pintype "passive"))
      (node (ref "U$8") (pin "1") (pinfunction "A_1") (pintype "bidirectional"))
    )
    (net (code "34") (name "ENC_B") (class "Default")
      (node (ref "IC4") (pin "6") (pinfunction "PD4(XCK/T0)_6") (pintype "bidirectional"))
      (node (ref "R21") (pin "1") (pinfunction "1_1") (pintype "passive"))
      (node (ref "U$8") (pin "3") (pinfunction "B_3") (pintype "bidirectional"))
    )
    (net (code "35") (name "ENC_SW") (class "Default")
      (node (ref "IC4") (pin "4") (pinfunction "PD2(INT0)_4") (pintype "bidirectional"))
      (node (ref "R23") (pin "1") (pinfunction "1_1") (pintype "passive"))
      (node (ref "U$8") (pin "2") (pinfunction "SW+_2") (pintype "bidirectional"))
    )
    (net (code "36") (name "ERTH") (class "Default")
      (node (ref "X1") (pin "5") (pinfunction "S_5") (pintype "passive"))
    )
    (net (code "37") (name "E_A") (class "Default")
      (node (ref "IC5") (pin "5") (pinfunction "PD3(INT1)_5") (pintype "bidirectional"))
      (node (ref "R40") (pin "1") (pinfunction "1_1") (pintype "passive"))
      (node (ref "U$11") (pin "3") (pinfunction "B_3") (pintype "bidirectional"))
    )
    (net (code "38") (name "E_B") (class "Default")
      (node (ref "IC5") (pin "6") (pinfunction "PD4(XCK/T0)_6") (pintype "bidirectional"))
      (node (ref "R41") (pin "1") (pinfunction "1_1") (pintype "passive"))
      (node (ref "U$11") (pin "1") (pinfunction "A_1") (pintype "bidirectional"))
    )
    (net (code "39") (name "E_SW") (class "Default")
      (node (ref "IC5") (pin "4") (pinfunction "PD2(INT0)_4") (pintype "bidirectional"))
      (node (ref "R42") (pin "1") (pinfunction "1_1") (pintype "passive"))
      (node (ref "U$11") (pin "2") (pinfunction "SW+_2") (pintype "bidirectional"))
    )
    (net (code "40") (name "GND") (class "Default")
      (node (ref "B1") (pin "-") (pinfunction "-_-") (pintype "passive"))
      (node (ref "C1") (pin "2") (pinfunction "2_2") (pintype "passive"))
      (node (ref "C10") (pin "2") (pinfunction "-_2") (pintype "passive"))
      (node (ref "C11") (pin "2") (pinfunction "2_2") (pintype "passive"))
      (node (ref "C12") (pin "2") (pinfunction "-_2") (pintype "passive"))
      (node (ref "C13") (pin "2") (pinfunction "-_2") (pintype "passive"))
      (node (ref "C14") (pin "2") (pinfunction "2_2") (pintype "passive"))
      (node (ref "C15") (pin "2") (pinfunction "2_2") (pintype "passive"))
      (node (ref "C2") (pin "2") (pinfunction "2_2") (pintype "passive"))
      (node (ref "C3") (pin "2") (pinfunction "2_2") (pintype "passive"))
      (node (ref "C4") (pin "2") (pinfunction "2_2") (pintype "passive"))
      (node (ref "C6") (pin "1") (pinfunction "1_1") (pintype "passive"))
      (node (ref "C7") (pin "2") (pinfunction "2_2") (pintype "passive"))
      (node (ref "C8") (pin "2") (pinfunction "2_2") (pintype "passive"))
      (node (ref "C9") (pin "2") (pinfunction "-_2") (pintype "passive"))
      (node (ref "D1") (pin "A") (pinfunction "A_A") (pintype "passive"))
      (node (ref "IC1") (pin "13") (pinfunction "G_13") (pintype "input"))
      (node (ref "IC1") (pin "8") (pinfunction "GND_8") (pintype "power_in"))
      (node (ref "IC2") (pin "13") (pinfunction "G_13") (pintype "input"))
      (node (ref "IC2") (pin "8") (pinfunction "GND_8") (pintype "power_in"))
      (node (ref "IC3") (pin "22") (pinfunction "AGND_22") (pintype "bidirectional"))
      (node (ref "IC3") (pin "8") (pinfunction "GND_8") (pintype "bidirectional"))
      (node (ref "IC4") (pin "22") (pinfunction "AGND_22") (pintype "bidirectional"))
      (node (ref "IC4") (pin "8") (pinfunction "GND_8") (pintype "bidirectional"))
      (node (ref "IC5") (pin "22") (pinfunction "AGND_22") (pintype "bidirectional"))
      (node (ref "IC5") (pin "8") (pinfunction "GND_8") (pintype "bidirectional"))
      (node (ref "JP1") (pin "1") (pinfunction "1_1") (pintype "passive"))
      (node (ref "JP10") (pin "2") (pinfunction "2_2") (pintype "passive"))
      (node (ref "JP11") (pin "2") (pinfunction "2_2") (pintype "passive"))
      (node (ref "JP12") (pin "2") (pinfunction "2_2") (pintype "passive"))
      (node (ref "JP2") (pin "P$1") (pinfunction "1_P$1") (pintype "passive"))
      (node (ref "JP3") (pin "P$1") (pinfunction "1_P$1") (pintype "passive"))
      (node (ref "JP5") (pin "1") (pinfunction "1_1") (pintype "passive"))
      (node (ref "JP6") (pin "1") (pinfunction "1_1") (pintype "passive"))
      (node (ref "JP7") (pin "P$1") (pinfunction "1_P$1") (pintype "passive"))
      (node (ref "JP8") (pin "P$1") (pinfunction "1_P$1") (pintype "passive"))
      (node (ref "JP9") (pin "P$1") (pinfunction "1_P$1") (pintype "passive"))
      (node (ref "LED1") (pin "K") (pinfunction "C_K") (pintype "passive"))
      (node (ref "LED2") (pin "K") (pinfunction "C_K") (pintype "passive"))
      (node (ref "OK1") (pin "2") (pinfunction "C_2") (pintype "passive"))
      (node (ref "R20") (pin "1") (pinfunction "1_1") (pintype "passive"))
      (node (ref "R30") (pin "1") (pinfunction "1_1") (pintype "passive"))
      (node (ref "R31") (pin "1") (pinfunction "1_1") (pintype "passive"))
      (node (ref "R35") (pin "2") (pinfunction "2_2") (pintype "passive"))
      (node (ref "R38") (pin "1") (pinfunction "1_1") (pintype "passive"))
      (node (ref "R43") (pin "1") (pinfunction "1_1") (pintype "passive"))
      (node (ref "R44") (pin "1") (pinfunction "1_1") (pintype "passive"))
      (node (ref "U$11") (pin "4") (pinfunction "C_4") (pintype "bidirectional"))
      (node (ref "U$11") (pin "5") (pinfunction "SW-_5") (pintype "bidirectional"))
      (node (ref "U$12") (pin "4") (pinfunction "V-_4") (pintype "power_in"))
      (node (ref "U$8") (pin "4") (pinfunction "C_4") (pintype "bidirectional"))
      (node (ref "U$8") (pin "5") (pinfunction "SW-_5") (pintype "bidirectional"))
      (node (ref "U$9") (pin "1") (pinfunction "VSS_1") (pintype "power_in"))
      (node (ref "U$9") (pin "20") (pinfunction "K_20") (pintype "power_in"))
      (node (ref "U1") (pin "4") (pinfunction "GND_4") (pintype "bidirectional"))
      (node (ref "X1") (pin "4") (pinfunction "S_4") (pintype "passive"))
    )
    (net (code "41") (name "LCD_BL") (class "Default")
      (node (ref "IC3") (pin "15") (pinfunction "PB1(OC1A)_15") (pintype "bidirectional"))
      (node (ref "R14") (pin "1") (pinfunction "1_1") (pintype "passive"))
    )
    (net (code "42") (name "LEDA") (class "Default")
      (node (ref "IC4") (pin "25") (pinfunction "PC2(ADC2)_25") (pintype "bidirectional"))
      (node (ref "R24") (pin "2") (pinfunction "2_2") (pintype "passive"))
    )
    (net (code "43") (name "LEDB") (class "Default")
      (node (ref "IC4") (pin "24") (pinfunction "PC1(ADC1)_24") (pintype "bidirectional"))
      (node (ref "R25") (pin "2") (pinfunction "2_2") (pintype "passive"))
    )
    (net (code "44") (name "Net-(C5-Pad1)") (class "Default")
      (node (ref "C5") (pin "1") (pinfunction "1_1") (pintype "passive"))
      (node (ref "R27") (pin "2") (pinfunction "2_2") (pintype "passive"))
      (node (ref "R28") (pin "1") (pinfunction "1_1") (pintype "passive"))
    )
    (net (code "45") (name "Net-(C10-+)") (class "Default")
      (node (ref "B1") (pin "+") (pinfunction "+_+") (pintype "passive"))
      (node (ref "C10") (pin "1") (pinfunction "+_1") (pintype "passive"))
      (node (ref "C11") (pin "1") (pinfunction "1_1") (pintype "passive"))
      (node (ref "C9") (pin "1") (pinfunction "+_1") (pintype "passive"))
      (node (ref "U1") (pin "1") (pinfunction "SWC_1") (pintype "bidirectional"))
      (node (ref "U1") (pin "6") (pinfunction "VCC_6") (pintype "bidirectional"))
      (node (ref "U1") (pin "7") (pinfunction "SEN_7") (pintype "bidirectional"))
      (node (ref "U1") (pin "8") (pinfunction "DVR_8") (pintype "bidirectional"))
    )
    (net (code "46") (name "Net-(C12-+)") (class "Default")
      (node (ref "C12") (pin "1") (pinfunction "+_1") (pintype "passive"))
      (node (ref "L1") (pin "2") (pinfunction "2_2") (pintype "passive"))
      (node (ref "L2") (pin "1") (pinfunction "1_1") (pintype "passive"))
    )
    (net (code "47") (name "Net-(C16-+)") (class "Default")
      (node (ref "C16") (pin "1") (pinfunction "+_1") (pintype "passive"))
      (node (ref "IC6") (pin "1") (pinfunction "VIN_1") (pintype "input"))
      (node (ref "JP16") (pin "1") (pinfunction "1_1") (pintype "passive"))
      (node (ref "L3") (pin "2") (pinfunction "2_2") (pintype "passive"))
    )
    (net (code "48") (name "Net-(C16--)") (class "Default")
      (node (ref "C16") (pin "2") (pinfunction "-_2") (pintype "passive"))
      (node (ref "C17") (pin "2") (pinfunction "-_2") (pintype "passive"))
      (node (ref "D2") (pin "A") (pinfunction "A_A") (pintype "passive"))
      (node (ref "IC6") (pin "3") (pinfunction "GND_3") (pintype "power_in"))
      (node (ref "IC6") (pin "5") (pinfunction "~{ON}/OFF_5") (pintype "input"))
      (node (ref "JP14") (pin "1") (pinfunction "1_1") (pintype "passive"))
      (node (ref "JP17") (pin "1") (pinfunction "1_1") (pintype "passive"))
      (node (ref "R60") (pin "1") (pinfunction "1_1") (pintype "passive"))
    )
    (net (code "49") (name "Net-(C17-+)") (class "Default")
      (node (ref "C17") (pin "1") (pinfunction "+_1") (pintype "passive"))
      (node (ref "L4") (pin "2") (pinfunction "2_2") (pintype "passive"))
      (node (ref "R54") (pin "1") (pinfunction "1_1") (pintype "passive"))
      (node (ref "T1") (pin "E") (pinfunction "E_E") (pintype "passive"))
    )
    (net (code "50") (name "Net-(D3-PadA)") (class "Default")
      (node (ref "D3") (pin "A") (pinfunction "A_A") (pintype "passive"))
      (node (ref "JP13") (pin "1") (pinfunction "1_1") (pintype "passive"))
    )
    (net (code "51") (name "Net-(D3-PadC)") (class "Default")
      (node (ref "D3") (pin "C") (pinfunction "C_C") (pintype "passive"))
      (node (ref "L3") (pin "1") (pinfunction "1_1") (pintype "passive"))
    )
    (net (code "52") (name "Net-(IC1-QA)") (class "Default")
      (node (ref "IC1") (pin "15") (pinfunction "QA_15") (pintype "tri_state"))
      (node (ref "R1") (pin "1") (pinfunction "1_1") (pintype "passive"))
    )
    (net (code "53") (name "Net-(IC1-QB)") (class "Default")
      (node (ref "IC1") (pin "1") (pinfunction "QB_1") (pintype "tri_state"))
      (node (ref "R2") (pin "1") (pinfunction "1_1") (pintype "passive"))
    )
    (net (code "54") (name "Net-(IC1-QC)") (class "Default")
      (node (ref "IC1") (pin "2") (pinfunction "QC_2") (pintype "tri_state"))
      (node (ref "R3") (pin "1") (pinfunction "1_1") (pintype "passive"))
    )
    (net (code "55") (name "Net-(IC1-QD)") (class "Default")
      (node (ref "IC1") (pin "3") (pinfunction "QD_3") (pintype "tri_state"))
      (node (ref "R4") (pin "1") (pinfunction "1_1") (pintype "passive"))
    )
    (net (code "56") (name "Net-(IC1-QE)") (class "Default")
      (node (ref "IC1") (pin "4") (pinfunction "QE_4") (pintype "tri_state"))
      (node (ref "R5") (pin "1") (pinfunction "1_1") (pintype "passive"))
    )
    (net (code "57") (name "Net-(IC1-QF)") (class "Default")
      (node (ref "IC1") (pin "5") (pinfunction "QF_5") (pintype "tri_state"))
      (node (ref "R6") (pin "1") (pinfunction "1_1") (pintype "passive"))
    )
    (net (code "58") (name "Net-(IC1-QG)") (class "Default")
      (node (ref "IC1") (pin "6") (pinfunction "QG_6") (pintype "tri_state"))
      (node (ref "R7") (pin "1") (pinfunction "1_1") (pintype "passive"))
    )
    (net (code "59") (name "Net-(IC1-QH)") (class "Default")
      (node (ref "IC1") (pin "7") (pinfunction "QH_7") (pintype "tri_state"))
      (node (ref "R8") (pin "1") (pinfunction "1_1") (pintype "passive"))
    )
    (net (code "60") (name "Net-(IC1-QH*)") (class "Default")
      (node (ref "IC1") (pin "9") (pinfunction "QH*_9") (pintype "tri_state"))
      (node (ref "IC2") (pin "14") (pinfunction "SER_14") (pintype "input"))
    )
    (net (code "61") (name "Net-(IC1-RCK)") (class "Default")
      (node (ref "IC1") (pin "12") (pinfunction "RCK_12") (pintype "input"))
      (node (ref "IC2") (pin "12") (pinfunction "RCK_12") (pintype "input"))
      (node (ref "JP5") (pin "2") (pinfunction "2_2") (pintype "passive"))
      (node (ref "JP6") (pin "2") (pinfunction "2_2") (pintype "passive"))
    )
    (net (code "62") (name "Net-(IC1-SCK)") (class "Default")
      (node (ref "IC1") (pin "11") (pinfunction "SCK_11") (pintype "input"))
      (node (ref "IC2") (pin "11") (pinfunction "SCK_11") (pintype "input"))
      (node (ref "JP5") (pin "3") (pinfunction "3_3") (pintype "passive"))
      (node (ref "JP6") (pin "3") (pinfunction "3_3") (pintype "passive"))
    )
    (net (code "63") (name "Net-(IC1-SER)") (class "Default")
      (node (ref "IC1") (pin "14") (pinfunction "SER_14") (pintype "input"))
      (node (ref "JP5") (pin "4") (pinfunction "4_4") (pintype "passive"))
    )
    (net (code "64") (name "Net-(IC2-QE)") (class "Default")
      (node (ref "IC2") (pin "4") (pinfunction "QE_4") (pintype "tri_state"))
      (node (ref "R9") (pin "1") (pinfunction "1_1") (pintype "passive"))
    )
    (net (code "65") (name "Net-(IC2-QF)") (class "Default")
      (node (ref "IC2") (pin "5") (pinfunction "QF_5") (pintype "tri_state"))
      (node (ref "R10") (pin "1") (pinfunction "1_1") (pintype "passive"))
    )
    (net (code "66") (name "Net-(IC2-QG)") (class "Default")
      (node (ref "IC2") (pin "6") (pinfunction "QG_6") (pintype "tri_state"))
      (node (ref "R11") (pin "1") (pinfunction "1_1") (pintype "passive"))
    )
    (net (code "67") (name "Net-(IC2-QH)") (class "Default")
      (node (ref "IC2") (pin "7") (pinfunction "QH_7") (pintype "tri_state"))
      (node (ref "R12") (pin "1") (pinfunction "1_1") (pintype "passive"))
    )
    (net (code "68") (name "Net-(IC5-PC0(ADC0))") (class "Default")
      (node (ref "IC5") (pin "23") (pinfunction "PC0(ADC0)_23") (pintype "bidirectional"))
      (node (ref "R45") (pin "2") (pinfunction "2_2") (pintype "passive"))
    )
    (net (code "69") (name "Net-(IC5-PC1(ADC1))") (class "Default")
      (node (ref "IC5") (pin "24") (pinfunction "PC1(ADC1)_24") (pintype "bidirectional"))
      (node (ref "R46") (pin "2") (pinfunction "2_2") (pintype "passive"))
    )
    (net (code "70") (name "Net-(IC5-PC2(ADC2))") (class "Default")
      (node (ref "IC5") (pin "25") (pinfunction "PC2(ADC2)_25") (pintype "bidirectional"))
      (node (ref "R47") (pin "2") (pinfunction "2_2") (pintype "passive"))
    )
    (net (code "71") (name "Net-(IC5-PC3(ADC3))") (class "Default")
      (node (ref "IC5") (pin "26") (pinfunction "PC3(ADC3)_26") (pintype "bidirectional"))
      (node (ref "R48") (pin "2") (pinfunction "2_2") (pintype "passive"))
    )
    (net (code "72") (name "Net-(IC5-PC4(ADC4{slash}SDA))") (class "Default")
      (node (ref "IC5") (pin "27") (pinfunction "PC4(ADC4/SDA)_27") (pintype "bidirectional"))
      (node (ref "R49") (pin "2") (pinfunction "2_2") (pintype "passive"))
    )
    (net (code "73") (name "Net-(IC5-PD1(TXD))") (class "Default")
      (node (ref "IC5") (pin "3") (pinfunction "PD1(TXD)_3") (pintype "bidirectional"))
      (node (ref "JP11") (pin "1") (pinfunction "1_1") (pintype "passive"))
    )
    (net (code "74") (name "Net-(IC5-PD5(T1))") (class "Default")
      (node (ref "IC5") (pin "11") (pinfunction "PD5(T1)_11") (pintype "bidirectional"))
      (node (ref "R55") (pin "2") (pinfunction "2_2") (pintype "passive"))
    )
    (net (code "75") (name "Net-(IC5-PD6(AIN0))") (class "Default")
      (node (ref "IC5") (pin "12") (pinfunction "PD6(AIN0)_12") (pintype "bidirectional"))
      (node (ref "R52") (pin "2") (pinfunction "2_2") (pintype "passive"))
    )
    (net (code "76") (name "Net-(IC6-FB)") (class "Default")
      (node (ref "IC6") (pin "4") (pinfunction "FB_4") (pintype "input"))
      (node (ref "R60") (pin "2") (pinfunction "2_2") (pintype "passive"))
      (node (ref "T1") (pin "C") (pinfunction "C_C") (pintype "passive"))
    )
    (net (code "77") (name "Net-(IC6-OUT)") (class "Default")
      (node (ref "D2") (pin "C") (pinfunction "C_C") (pintype "passive"))
      (node (ref "IC6") (pin "2") (pinfunction "OUT_2") (pintype "output"))
      (node (ref "L4") (pin "1") (pinfunction "1_1") (pintype "passive"))
    )
    (net (code "78") (name "Net-(IC7-R)") (class "Default")
      (node (ref "IC7") (pin "2") (pinfunction "R_2") (pintype "passive"))
      (node (ref "Q6") (pin "3") (pinfunction "E_3") (pintype "passive"))
      (node (ref "U$10") (pin "2") (pinfunction "E_2") (pintype "passive"))
    )
    (net (code "79") (name "Net-(IC7-V+)") (class "Default")
      (node (ref "IC7") (pin "1") (pinfunction "V+_1") (pintype "passive"))
      (node (ref "R32") (pin "1") (pinfunction "1_1") (pintype "passive"))
      (node (ref "U$10") (pin "1") (pinfunction "S_1") (pintype "passive"))
      (node (ref "U$10") (pin "3") (pinfunction "A_3") (pintype "passive"))
    )
    (net (code "80") (name "Net-(IC7-V-)") (class "Default")
      (node (ref "IC7") (pin "3") (pinfunction "V-_3") (pintype "passive"))
      (node (ref "Q6") (pin "2") (pinfunction "B_2") (pintype "passive"))
      (node (ref "R31") (pin "2") (pinfunction "2_2") (pintype "passive"))
    )
    (net (code "81") (name "Net-(JP10-Pad1)") (class "Default")
      (node (ref "JP10") (pin "1") (pinfunction "1_1") (pintype "passive"))
      (node (ref "R52") (pin "1") (pinfunction "1_1") (pintype "passive"))
    )
    (net (code "82") (name "Net-(JP12-Pad1)") (class "Default")
      (node (ref "JP12") (pin "1") (pinfunction "1_1") (pintype "passive"))
      (node (ref "R53") (pin "1") (pinfunction "1_1") (pintype "passive"))
    )
    (net (code "83") (name "Net-(JP15-Pad1)") (class "Default")
      (node (ref "JP15") (pin "1") (pinfunction "1_1") (pintype "passive"))
      (node (ref "R54") (pin "2") (pinfunction "2_2") (pintype "passive"))
      (node (ref "R57") (pin "2") (pinfunction "2_2") (pintype "passive"))
    )
    (net (code "84") (name "Net-(LED1-PadA)") (class "Default")
      (node (ref "LED1") (pin "A") (pinfunction "A_A") (pintype "passive"))
      (node (ref "R24") (pin "1") (pinfunction "1_1") (pintype "passive"))
    )
    (net (code "85") (name "Net-(LED2-PadA)") (class "Default")
      (node (ref "LED2") (pin "A") (pinfunction "A_A") (pintype "passive"))
      (node (ref "R25") (pin "1") (pinfunction "1_1") (pintype "passive"))
    )
    (net (code "86") (name "Net-(LED3-C)") (class "Default")
      (node (ref "LED3") (pin "K") (pinfunction "C_K") (pintype "passive"))
      (node (ref "R43") (pin "2") (pinfunction "2_2") (pintype "passive"))
    )
    (net (code "87") (name "Net-(LED4-C)") (class "Default")
      (node (ref "LED4") (pin "K") (pinfunction "C_K") (pintype "passive"))
      (node (ref "R44") (pin "2") (pinfunction "2_2") (pintype "passive"))
    )
    (net (code "88") (name "Net-(OK1-A)") (class "Default")
      (node (ref "OK1") (pin "1") (pinfunction "A_1") (pintype "passive"))
      (node (ref "R34") (pin "1") (pinfunction "1_1") (pintype "passive"))
    )
    (net (code "89") (name "Net-(OK1-A1)") (class "Default")
      (node (ref "OK1") (pin "4") (pinfunction "A1_4") (pintype "passive"))
      (node (ref "T2") (pin "G") (pinfunction "G_G") (pintype "passive"))
    )
    (net (code "90") (name "Net-(OK1-A2)") (class "Default")
      (node (ref "OK1") (pin "6") (pinfunction "A2_6") (pintype "passive"))
      (node (ref "R33") (pin "2") (pinfunction "2_2") (pintype "passive"))
    )
    (net (code "91") (name "Net-(Q1-B)") (class "Default")
      (node (ref "Q1") (pin "1") (pinfunction "B_1") (pintype "passive"))
      (node (ref "R9") (pin "2") (pinfunction "2_2") (pintype "passive"))
    )
    (net (code "92") (name "Net-(Q1-C)") (class "Default")
      (node (ref "Q1") (pin "3") (pinfunction "C_3") (pintype "passive"))
      (node (ref "U$3") (pin "3") (pinfunction "G1_3") (pintype "bidirectional"))
      (node (ref "U$3") (pin "8") (pinfunction "G2_8") (pintype "bidirectional"))
    )
    (net (code "93") (name "Net-(Q2-B)") (class "Default")
      (node (ref "Q2") (pin "1") (pinfunction "B_1") (pintype "passive"))
      (node (ref "R10") (pin "2") (pinfunction "2_2") (pintype "passive"))
    )
    (net (code "94") (name "Net-(Q2-C)") (class "Default")
      (node (ref "Q2") (pin "3") (pinfunction "C_3") (pintype "passive"))
      (node (ref "U$1") (pin "3") (pinfunction "G1_3") (pintype "bidirectional"))
      (node (ref "U$1") (pin "8") (pinfunction "G2_8") (pintype "bidirectional"))
    )
    (net (code "95") (name "Net-(Q3-B)") (class "Default")
      (node (ref "Q3") (pin "1") (pinfunction "B_1") (pintype "passive"))
      (node (ref "R11") (pin "2") (pinfunction "2_2") (pintype "passive"))
    )
    (net (code "96") (name "Net-(Q3-C)") (class "Default")
      (node (ref "Q3") (pin "3") (pinfunction "C_3") (pintype "passive"))
      (node (ref "U$2") (pin "3") (pinfunction "G1_3") (pintype "bidirectional"))
      (node (ref "U$2") (pin "8") (pinfunction "G2_8") (pintype "bidirectional"))
    )
    (net (code "97") (name "Net-(Q4-B)") (class "Default")
      (node (ref "Q4") (pin "1") (pinfunction "B_1") (pintype "passive"))
      (node (ref "R12") (pin "2") (pinfunction "2_2") (pintype "passive"))
    )
    (net (code "98") (name "Net-(Q4-C)") (class "Default")
      (node (ref "Q4") (pin "3") (pinfunction "C_3") (pintype "passive"))
      (node (ref "U$4") (pin "3") (pinfunction "G1_3") (pintype "bidirectional"))
      (node (ref "U$4") (pin "8") (pinfunction "G2_8") (pintype "bidirectional"))
    )
    (net (code "99") (name "Net-(Q5-B)") (class "Default")
      (node (ref "Q5") (pin "1") (pinfunction "B_1") (pintype "passive"))
      (node (ref "R14") (pin "2") (pinfunction "2_2") (pintype "passive"))
    )
    (net (code "100") (name "Net-(R15-Pad1)") (class "Default")
      (node (ref "R15") (pin "1") (pinfunction "1_1") (pintype "passive"))
      (node (ref "S1") (pin "1") (pinfunction "1_1") (pintype "passive"))
      (node (ref "S3") (pin "1") (pinfunction "1_1") (pintype "passive"))
      (node (ref "S5") (pin "1") (pinfunction "1_1") (pintype "passive"))
    )
    (net (code "101") (name "Net-(R57-Pad1)") (class "Default")
      (node (ref "R57") (pin "1") (pinfunction "1_1") (pintype "passive"))
      (node (ref "T1") (pin "B") (pinfunction "B_B") (pintype "passive"))
    )
    (net (code "102") (name "Net-(S1-2)") (class "Default")
      (node (ref "R17") (pin "2") (pinfunction "2_2") (pintype "passive"))
      (node (ref "S1") (pin "3") (pinfunction "2_3") (pintype "passive"))
      (node (ref "S2") (pin "1") (pinfunction "1_1") (pintype "passive"))
    )
    (net (code "103") (name "Net-(S2-2)") (class "Default")
      (node (ref "R16") (pin "1") (pinfunction "1_1") (pintype "passive"))
      (node (ref "S2") (pin "3") (pinfunction "2_3") (pintype "passive"))
      (node (ref "S4") (pin "1") (pinfunction "1_1") (pintype "passive"))
      (node (ref "S6") (pin "1") (pinfunction "1_1") (pintype "passive"))
    )
    (net (code "104") (name "Net-(S3-2)") (class "Default")
      (node (ref "R18") (pin "2") (pinfunction "2_2") (pintype "passive"))
      (node (ref "S3") (pin "3") (pinfunction "2_3") (pintype "passive"))
      (node (ref "S4") (pin "3") (pinfunction "2_3") (pintype "passive"))
    )
    (net (code "105") (name "Net-(S5-2)") (class "Default")
      (node (ref "R19") (pin "2") (pinfunction "2_2") (pintype "passive"))
      (node (ref "S5") (pin "3") (pinfunction "2_3") (pintype "passive"))
      (node (ref "S6") (pin "3") (pinfunction "2_3") (pintype "passive"))
    )
    (net (code "106") (name "Net-(U$1-A)") (class "Default")
      (node (ref "R1") (pin "2") (pinfunction "2_2") (pintype "passive"))
      (node (ref "U$1") (pin "7") (pinfunction "A_7") (pintype "bidirectional"))
      (node (ref "U$2") (pin "7") (pinfunction "A_7") (pintype "bidirectional"))
      (node (ref "U$3") (pin "7") (pinfunction "A_7") (pintype "bidirectional"))
      (node (ref "U$4") (pin "7") (pinfunction "A_7") (pintype "bidirectional"))
    )
    (net (code "107") (name "Net-(U$1-B)") (class "Default")
      (node (ref "R2") (pin "2") (pinfunction "2_2") (pintype "passive"))
      (node (ref "U$1") (pin "6") (pinfunction "B_6") (pintype "bidirectional"))
      (node (ref "U$2") (pin "6") (pinfunction "B_6") (pintype "bidirectional"))
      (node (ref "U$3") (pin "6") (pinfunction "B_6") (pintype "bidirectional"))
      (node (ref "U$4") (pin "6") (pinfunction "B_6") (pintype "bidirectional"))
    )
    (net (code "108") (name "Net-(U$1-C)") (class "Default")
      (node (ref "R3") (pin "2") (pinfunction "2_2") (pintype "passive"))
      (node (ref "U$1") (pin "4") (pinfunction "C_4") (pintype "bidirectional"))
      (node (ref "U$2") (pin "4") (pinfunction "C_4") (pintype "bidirectional"))
      (node (ref "U$3") (pin "4") (pinfunction "C_4") (pintype "bidirectional"))
      (node (ref "U$4") (pin "4") (pinfunction "C_4") (pintype "bidirectional"))
    )
    (net (code "109") (name "Net-(U$1-D)") (class "Default")
      (node (ref "R4") (pin "2") (pinfunction "2_2") (pintype "passive"))
      (node (ref "U$1") (pin "2") (pinfunction "D_2") (pintype "bidirectional"))
      (node (ref "U$2") (pin "2") (pinfunction "D_2") (pintype "bidirectional"))
      (node (ref "U$3") (pin "2") (pinfunction "D_2") (pintype "bidirectional"))
      (node (ref "U$4") (pin "2") (pinfunction "D_2") (pintype "bidirectional"))
    )
    (net (code "110") (name "Net-(U$1-DP)") (class "Default")
      (node (ref "R8") (pin "2") (pinfunction "2_2") (pintype "passive"))
      (node (ref "U$1") (pin "5") (pinfunction "DP_5") (pintype "bidirectional"))
      (node (ref "U$2") (pin "5") (pinfunction "DP_5") (pintype "bidirectional"))
      (node (ref "U$3") (pin "5") (pinfunction "DP_5") (pintype "bidirectional"))
      (node (ref "U$4") (pin "5") (pinfunction "DP_5") (pintype "bidirectional"))
    )
    (net (code "111") (name "Net-(U$1-E)") (class "Default")
      (node (ref "R5") (pin "2") (pinfunction "2_2") (pintype "passive"))
      (node (ref "U$1") (pin "1") (pinfunction "E_1") (pintype "bidirectional"))
      (node (ref "U$2") (pin "1") (pinfunction "E_1") (pintype "bidirectional"))
      (node (ref "U$3") (pin "1") (pinfunction "E_1") (pintype "bidirectional"))
      (node (ref "U$4") (pin "1") (pinfunction "E_1") (pintype "bidirectional"))
    )
    (net (code "112") (name "Net-(U$1-F)") (class "Default")
      (node (ref "R6") (pin "2") (pinfunction "2_2") (pintype "passive"))
      (node (ref "U$1") (pin "9") (pinfunction "F_9") (pintype "bidirectional"))
      (node (ref "U$2") (pin "9") (pinfunction "F_9") (pintype "bidirectional"))
      (node (ref "U$3") (pin "9") (pinfunction "F_9") (pintype "bidirectional"))
      (node (ref "U$4") (pin "9") (pinfunction "F_9") (pintype "bidirectional"))
    )
    (net (code "113") (name "Net-(U$1-G)") (class "Default")
      (node (ref "R7") (pin "2") (pinfunction "2_2") (pintype "passive"))
      (node (ref "U$1") (pin "10") (pinfunction "G_10") (pintype "bidirectional"))
      (node (ref "U$2") (pin "10") (pinfunction "G_10") (pintype "bidirectional"))
      (node (ref "U$3") (pin "10") (pinfunction "G_10") (pintype "bidirectional"))
      (node (ref "U$4") (pin "10") (pinfunction "G_10") (pintype "bidirectional"))
    )
    (net (code "114") (name "Net-(U$6-A)") (class "Default")
      (node (ref "R29") (pin "2") (pinfunction "2_2") (pintype "passive"))
      (node (ref "U$6") (pin "3") (pinfunction "A_3") (pintype "passive"))
    )
    (net (code "115") (name "Net-(U$12A-+IN)") (class "Default")
      (node (ref "R29") (pin "1") (pinfunction "1_1") (pintype "passive"))
      (node (ref "R30") (pin "2") (pinfunction "2_2") (pintype "passive"))
      (node (ref "U$12") (pin "3") (pinfunction "+IN_3") (pintype "input"))
    )
    (net (code "116") (name "Net-(U$12A--IN)") (class "Default")
      (node (ref "C6") (pin "2") (pinfunction "2_2") (pintype "passive"))
      (node (ref "R28") (pin "2") (pinfunction "2_2") (pintype "passive"))
      (node (ref "U$12") (pin "2") (pinfunction "-IN_2") (pintype "input"))
    )
    (net (code "117") (name "Net-(U1-COMP)") (class "Default")
      (node (ref "R35") (pin "1") (pinfunction "1_1") (pintype "passive"))
      (node (ref "R36") (pin "1") (pinfunction "1_1") (pintype "passive"))
      (node (ref "U1") (pin "5") (pinfunction "COMP_5") (pintype "bidirectional"))
    )
    (net (code "118") (name "Net-(U1-SWE)") (class "Default")
      (node (ref "D1") (pin "C") (pinfunction "C_C") (pintype "passive"))
      (node (ref "L1") (pin "1") (pinfunction "1_1") (pintype "passive"))
      (node (ref "U1") (pin "2") (pinfunction "SWE_2") (pintype "bidirectional"))
    )
    (net (code "119") (name "Net-(U1-TC)") (class "Default")
      (node (ref "C14") (pin "1") (pinfunction "1_1") (pintype "passive"))
      (node (ref "U1") (pin "3") (pinfunction "TC_3") (pintype "bidirectional"))
    )
    (net (code "120") (name "PG_SCK") (class "Default")
      (node (ref "IC5") (pin "19") (pinfunction "PB5(SCK)_19") (pintype "bidirectional"))
      (node (ref "JP7") (pin "P$2") (pinfunction "2_P$2") (pintype "passive"))
      (node (ref "R50") (pin "2") (pinfunction "2_2") (pintype "passive"))
    )
    (net (code "121") (name "PG_SI") (class "Default")
      (node (ref "IC5") (pin "18") (pinfunction "PB4(MISO)_18") (pintype "bidirectional"))
      (node (ref "JP7") (pin "P$3") (pinfunction "3_P$3") (pintype "passive"))
      (node (ref "R51") (pin "2") (pinfunction "2_2") (pintype "passive"))
    )
    (net (code "122") (name "PG_SO") (class "Default")
      (node (ref "IC5") (pin "17") (pinfunction "PB3(MOSI/OC2)_17") (pintype "bidirectional"))
      (node (ref "JP7") (pin "P$4") (pinfunction "4_P$4") (pintype "passive"))
    )
    (net (code "123") (name "PTC+") (class "Default")
      (node (ref "Q6") (pin "1") (pinfunction "C_1") (pintype "passive"))
      (node (ref "R27") (pin "1") (pinfunction "1_1") (pintype "passive"))
      (node (ref "X1") (pin "3") (pinfunction "S_3") (pintype "passive"))
    )
    (net (code "124") (name "RESET") (class "Default")
      (node (ref "IC3") (pin "14") (pinfunction "PB0(ICP)_14") (pintype "bidirectional"))
      (node (ref "U$9") (pin "17") (pinfunction "RST_17") (pintype "input"))
    )
    (net (code "125") (name "RST") (class "Default")
      (node (ref "IC5") (pin "1") (pinfunction "PC6(/RESET)_1") (pintype "bidirectional"))
      (node (ref "JP7") (pin "P$5") (pinfunction "5_P$5") (pintype "passive"))
      (node (ref "R39") (pin "2") (pinfunction "2_2") (pintype "passive"))
    )
    (net (code "126") (name "RST0") (class "Default")
      (node (ref "IC4") (pin "1") (pinfunction "PC6(/RESET)_1") (pintype "bidirectional"))
      (node (ref "JP3") (pin "P$5") (pinfunction "5_P$5") (pintype "passive"))
      (node (ref "R13") (pin "2") (pinfunction "2_2") (pintype "passive"))
    )
    (net (code "127") (name "RST1") (class "Default")
      (node (ref "IC3") (pin "1") (pinfunction "PC6(/RESET)_1") (pintype "bidirectional"))
      (node (ref "JP2") (pin "P$5") (pinfunction "5_P$5") (pintype "passive"))
      (node (ref "R26") (pin "2") (pinfunction "2_2") (pintype "passive"))
    )
    (net (code "128") (name "RW") (class "Default")
      (node (ref "IC3") (pin "27") (pinfunction "PC4(ADC4/SDA)_27") (pintype "bidirectional"))
      (node (ref "U$9") (pin "5") (pinfunction "R/W_5") (pintype "input"))
    )
    (net (code "129") (name "SCK") (class "Default")
      (node (ref "IC4") (pin "13") (pinfunction "PD7(AIN1)_13") (pintype "bidirectional"))
      (node (ref "JP1") (pin "3") (pinfunction "3_3") (pintype "passive"))
    )
    (net (code "130") (name "SDO1") (class "Default")
      (node (ref "IC2") (pin "9") (pinfunction "QH*_9") (pintype "tri_state"))
      (node (ref "JP6") (pin "4") (pinfunction "4_4") (pintype "passive"))
    )
    (net (code "131") (name "SO") (class "Default")
      (node (ref "IC4") (pin "12") (pinfunction "PD6(AIN0)_12") (pintype "bidirectional"))
      (node (ref "JP1") (pin "4") (pinfunction "4_4") (pintype "passive"))
    )
    (net (code "132") (name "SPI_CK0") (class "Default")
      (node (ref "IC4") (pin "19") (pinfunction "PB5(SCK)_19") (pintype "bidirectional"))
      (node (ref "JP3") (pin "P$2") (pinfunction "2_P$2") (pintype "passive"))
      (node (ref "JP8") (pin "P$2") (pinfunction "2_P$2") (pintype "passive"))
    )
    (net (code "133") (name "SPI_CK1") (class "Default")
      (node (ref "IC3") (pin "19") (pinfunction "PB5(SCK)_19") (pintype "bidirectional"))
      (node (ref "JP2") (pin "P$2") (pinfunction "2_P$2") (pintype "passive"))
      (node (ref "JP9") (pin "P$2") (pinfunction "2_P$2") (pintype "passive"))
    )
    (net (code "134") (name "SPI_CS0") (class "Default")
      (node (ref "IC4") (pin "16") (pinfunction "PB2(SS/OC1B)_16") (pintype "bidirectional"))
      (node (ref "JP8") (pin "P$5") (pinfunction "5_P$5") (pintype "passive"))
    )
    (net (code "135") (name "SPI_CS1") (class "Default")
      (node (ref "IC3") (pin "16") (pinfunction "PB2(SS/OC1B)_16") (pintype "bidirectional"))
      (node (ref "JP9") (pin "P$5") (pinfunction "5_P$5") (pintype "passive"))
    )
    (net (code "136") (name "SPI_SI0") (class "Default")
      (node (ref "IC4") (pin "18") (pinfunction "PB4(MISO)_18") (pintype "bidirectional"))
      (node (ref "JP3") (pin "P$3") (pinfunction "3_P$3") (pintype "passive"))
      (node (ref "JP8") (pin "P$3") (pinfunction "3_P$3") (pintype "passive"))
    )
    (net (code "137") (name "SPI_SI1") (class "Default")
      (node (ref "IC3") (pin "18") (pinfunction "PB4(MISO)_18") (pintype "bidirectional"))
      (node (ref "JP2") (pin "P$3") (pinfunction "3_P$3") (pintype "passive"))
      (node (ref "JP9") (pin "P$3") (pinfunction "3_P$3") (pintype "passive"))
    )
    (net (code "138") (name "SPI_SO0") (class "Default")
      (node (ref "IC4") (pin "17") (pinfunction "PB3(MOSI/OC2)_17") (pintype "bidirectional"))
      (node (ref "JP3") (pin "P$4") (pinfunction "4_P$4") (pintype "passive"))
      (node (ref "JP8") (pin "P$4") (pinfunction "4_P$4") (pintype "passive"))
    )
    (net (code "139") (name "SPI_SO1") (class "Default")
      (node (ref "IC3") (pin "17") (pinfunction "PB3(MOSI/OC2)_17") (pintype "bidirectional"))
      (node (ref "JP2") (pin "P$4") (pinfunction "4_P$4") (pintype "passive"))
      (node (ref "JP9") (pin "P$4") (pinfunction "4_P$4") (pintype "passive"))
    )
    (net (code "140") (name "SS1") (class "Default")
      (node (ref "IC4") (pin "14") (pinfunction "PB0(ICP)_14") (pintype "bidirectional"))
      (node (ref "JP1") (pin "2") (pinfunction "2_2") (pintype "passive"))
    )
    (net (code "141") (name "T2") (class "Default")
      (node (ref "R33") (pin "1") (pinfunction "1_1") (pintype "passive"))
      (node (ref "T2") (pin "T2") (pinfunction "A2_T2") (pintype "passive"))
      (node (ref "X1") (pin "2") (pinfunction "S_2") (pintype "passive"))
    )
    (net (code "142") (name "TRIAC_EN") (class "Default")
      (node (ref "IC5") (pin "2") (pinfunction "PD0(RXD)_2") (pintype "bidirectional"))
      (node (ref "LED4") (pin "A") (pinfunction "A_A") (pintype "passive"))
      (node (ref "R34") (pin "2") (pinfunction "2_2") (pintype "passive"))
    )
    (net (code "143") (name "TSENSE") (class "Default")
      (node (ref "C5") (pin "2") (pinfunction "2_2") (pintype "passive"))
      (node (ref "IC5") (pin "28") (pinfunction "PC5(ADC5/SCL)_28") (pintype "bidirectional"))
      (node (ref "U$12") (pin "1") (pinfunction "OUT_1") (pintype "output"))
      (node (ref "U$6") (pin "1") (pinfunction "S_1") (pintype "passive"))
      (node (ref "U$6") (pin "2") (pinfunction "E_2") (pintype "passive"))
    )
    (net (code "144") (name "VEE") (class "Default")
      (node (ref "U$7") (pin "3") (pinfunction "A_3") (pintype "passive"))
      (node (ref "U$9") (pin "18") (pinfunction "VEE_18") (pintype "bidirectional"))
    )
    (net (code "145") (name "VO") (class "Default")
      (node (ref "U$7") (pin "1") (pinfunction "S_1") (pintype "passive"))
      (node (ref "U$9") (pin "3") (pinfunction "VO_3") (pintype "bidirectional"))
    )
    (net (code "146") (name "unconnected-(IC2-QA-Pad15)") (class "Default")
      (node (ref "IC2") (pin "15") (pinfunction "QA_15") (pintype "tri_state"))
    )
    (net (code "147") (name "unconnected-(IC2-QB-Pad1)") (class "Default")
      (node (ref "IC2") (pin "1") (pinfunction "QB_1") (pintype "tri_state"))
    )
    (net (code "148") (name "unconnected-(IC2-QC-Pad2)") (class "Default")
      (node (ref "IC2") (pin "2") (pinfunction "QC_2") (pintype "tri_state"))
    )
    (net (code "149") (name "unconnected-(IC2-QD-Pad3)") (class "Default")
      (node (ref "IC2") (pin "3") (pinfunction "QD_3") (pintype "tri_state"))
    )
    (net (code "150") (name "unconnected-(IC3-PC0(ADC0)-Pad23)") (class "Default")
      (node (ref "IC3") (pin "23") (pinfunction "PC0(ADC0)_23") (pintype "bidirectional"))
    )
    (net (code "151") (name "unconnected-(IC3-PC1(ADC1)-Pad24)") (class "Default")
      (node (ref "IC3") (pin "24") (pinfunction "PC1(ADC1)_24") (pintype "bidirectional"))
    )
    (net (code "152") (name "unconnected-(IC3-PC2(ADC2)-Pad25)") (class "Default")
      (node (ref "IC3") (pin "25") (pinfunction "PC2(ADC2)_25") (pintype "bidirectional"))
    )
    (net (code "153") (name "unconnected-(IC4-PB1(OC1A)-Pad15)") (class "Default")
      (node (ref "IC4") (pin "15") (pinfunction "PB1(OC1A)_15") (pintype "bidirectional"))
    )
    (net (code "154") (name "unconnected-(IC4-PB6(XTAL1{slash}TOSC1)-Pad9)") (class "Default")
      (node (ref "IC4") (pin "9") (pinfunction "PB6(XTAL1/TOSC1)_9") (pintype "bidirectional"))
    )
    (net (code "155") (name "unconnected-(IC4-PB7(XTAL2{slash}TOSC2)-Pad10)") (class "Default")
      (node (ref "IC4") (pin "10") (pinfunction "PB7(XTAL2/TOSC2)_10") (pintype "bidirectional"))
    )
    (net (code "156") (name "unconnected-(IC4-PC3(ADC3)-Pad26)") (class "Default")
      (node (ref "IC4") (pin "26") (pinfunction "PC3(ADC3)_26") (pintype "bidirectional"))
    )
    (net (code "157") (name "unconnected-(IC4-PC4(ADC4{slash}SDA)-Pad27)") (class "Default")
      (node (ref "IC4") (pin "27") (pinfunction "PC4(ADC4/SDA)_27") (pintype "bidirectional"))
    )
    (net (code "158") (name "unconnected-(IC4-PD0(RXD)-Pad2)") (class "Default")
      (node (ref "IC4") (pin "2") (pinfunction "PD0(RXD)_2") (pintype "bidirectional"))
    )
    (net (code "159") (name "unconnected-(IC4-PD1(TXD)-Pad3)") (class "Default")
      (node (ref "IC4") (pin "3") (pinfunction "PD1(TXD)_3") (pintype "bidirectional"))
    )
    (net (code "160") (name "unconnected-(IC4-PD5(T1)-Pad11)") (class "Default")
      (node (ref "IC4") (pin "11") (pinfunction "PD5(T1)_11") (pintype "bidirectional"))
    )
    (net (code "161") (name "unconnected-(IC5-PB6(XTAL1{slash}TOSC1)-Pad9)") (class "Default")
      (node (ref "IC5") (pin "9") (pinfunction "PB6(XTAL1/TOSC1)_9") (pintype "bidirectional"))
    )
    (net (code "162") (name "unconnected-(IC5-PB7(XTAL2{slash}TOSC2)-Pad10)") (class "Default")
      (node (ref "IC5") (pin "10") (pinfunction "PB7(XTAL2/TOSC2)_10") (pintype "bidirectional"))
    )
  )
)
